# main.net
KiCad netlist of a schematic drawn in EAGLE
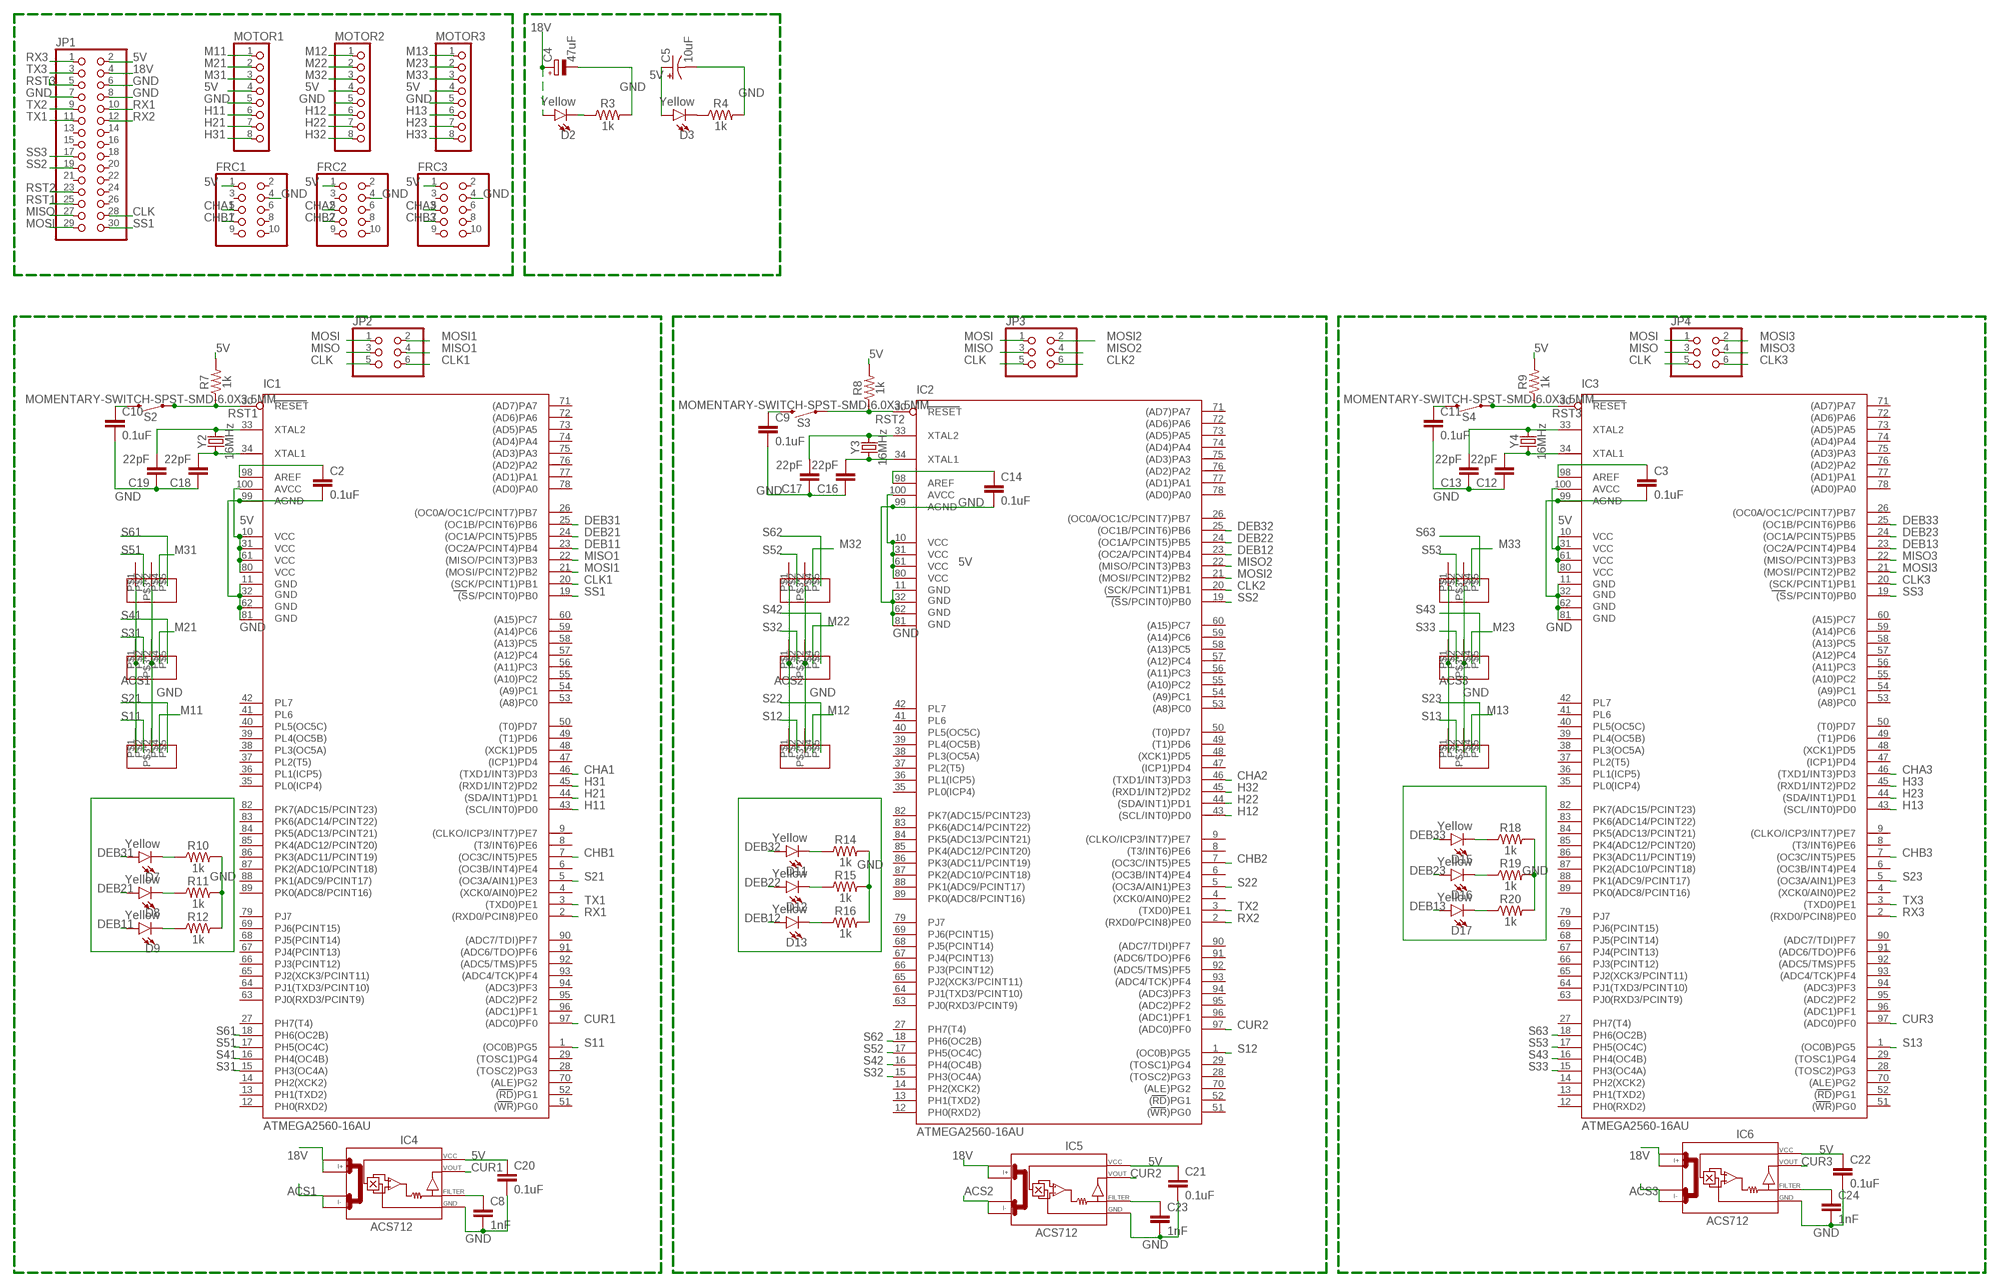
[diagram p0: schematic, sheet 1]

(export (version "E")
  (design (tool "Eeschema 10.0.6"))
  (components
    (comp (ref "C2")
      (value "0.1uF")
      (footprint "eagle-import:0603")
      (libsource (lib "eagle-import") (part "0.1UF-0603-25V-5%"))
    )
    (comp (ref "C3")
      (value "0.1uF")
      (footprint "eagle-import:0603")
      (libsource (lib "eagle-import") (part "0.1UF-0603-25V-5%"))
    )
    (comp (ref "C4")
      (value "47uF")
      (footprint "eagle-import:TAP5-60")
      (libsource (lib "eagle-import") (part "CPOL-EUTAP5-60"))
    )
    (comp (ref "C5")
      (value "10uF")
      (footprint "eagle-import:0603-POLAR")
      (libsource (lib "eagle-import") (part "10UF-POLAR-0603-6.3V-20%(TANT)"))
    )
    (comp (ref "C8")
      (value "1nF")
      (footprint "eagle-import:0603")
      (libsource (lib "eagle-import") (part "1.0NF/1000PF-0603-50V-10%"))
    )
    (comp (ref "C9")
      (value "0.1uF")
      (footprint "eagle-import:0603")
      (libsource (lib "eagle-import") (part "0.1UF-0603-25V-5%"))
    )
    (comp (ref "C10")
      (value "0.1uF")
      (footprint "eagle-import:0603")
      (libsource (lib "eagle-import") (part "0.1UF-0603-25V-5%"))
    )
    (comp (ref "C11")
      (value "0.1uF")
      (footprint "eagle-import:0603")
      (libsource (lib "eagle-import") (part "0.1UF-0603-25V-5%"))
    )
    (comp (ref "C12")
      (value "22pF")
      (footprint "eagle-import:0603")
      (libsource (lib "eagle-import") (part "22PF-0603-50V-5%"))
    )
    (comp (ref "C13")
      (value "22pF")
      (footprint "eagle-import:0603")
      (libsource (lib "eagle-import") (part "22PF-0603-50V-5%"))
    )
    (comp (ref "C14")
      (value "0.1uF")
      (footprint "eagle-import:0603")
      (libsource (lib "eagle-import") (part "0.1UF-0603-25V-5%"))
    )
    (comp (ref "C16")
      (value "22pF")
      (footprint "eagle-import:0603")
      (libsource (lib "eagle-import") (part "22PF-0603-50V-5%"))
    )
    (comp (ref "C17")
      (value "22pF")
      (footprint "eagle-import:0603")
      (libsource (lib "eagle-import") (part "22PF-0603-50V-5%"))
    )
    (comp (ref "C18")
      (value "22pF")
      (footprint "eagle-import:0603")
      (libsource (lib "eagle-import") (part "22PF-0603-50V-5%"))
    )
    (comp (ref "C19")
      (value "22pF")
      (footprint "eagle-import:0603")
      (libsource (lib "eagle-import") (part "22PF-0603-50V-5%"))
    )
    (comp (ref "C20")
      (value "0.1uF")
      (footprint "eagle-import:0603")
      (libsource (lib "eagle-import") (part "0.1UF-0603-25V-5%"))
    )
    (comp (ref "C21")
      (value "0.1uF")
      (footprint "eagle-import:0603")
      (libsource (lib "eagle-import") (part "0.1UF-0603-25V-5%"))
    )
    (comp (ref "C22")
      (value "0.1uF")
      (footprint "eagle-import:0603")
      (libsource (lib "eagle-import") (part "0.1UF-0603-25V-5%"))
    )
    (comp (ref "C23")
      (value "1nF")
      (footprint "eagle-import:0603")
      (libsource (lib "eagle-import") (part "1.0NF/1000PF-0603-50V-10%"))
    )
    (comp (ref "C24")
      (value "1nF")
      (footprint "eagle-import:0603")
      (libsource (lib "eagle-import") (part "1.0NF/1000PF-0603-50V-10%"))
    )
    (comp (ref "D2")
      (value "Yellow")
      (footprint "eagle-import:LED-0603")
      (libsource (lib "eagle-import") (part "LED-YELLOW0603"))
    )
    (comp (ref "D3")
      (value "Yellow")
      (footprint "eagle-import:LED-0603")
      (libsource (lib "eagle-import") (part "LED-YELLOW0603"))
    )
    (comp (ref "D7")
      (value "Yellow")
      (footprint "eagle-import:LED-0603")
      (libsource (lib "eagle-import") (part "LED-YELLOW0603"))
    )
    (comp (ref "D8")
      (value "Yellow")
      (footprint "eagle-import:LED-0603")
      (libsource (lib "eagle-import") (part "LED-YELLOW0603"))
    )
    (comp (ref "D9")
      (value "Yellow")
      (footprint "eagle-import:LED-0603")
      (libsource (lib "eagle-import") (part "LED-YELLOW0603"))
    )
    (comp (ref "D11")
      (value "Yellow")
      (footprint "eagle-import:LED-0603")
      (libsource (lib "eagle-import") (part "LED-YELLOW0603"))
    )
    (comp (ref "D12")
      (value "Yellow")
      (footprint "eagle-import:LED-0603")
      (libsource (lib "eagle-import") (part "LED-YELLOW0603"))
    )
    (comp (ref "D13")
      (value "Yellow")
      (footprint "eagle-import:LED-0603")
      (libsource (lib "eagle-import") (part "LED-YELLOW0603"))
    )
    (comp (ref "D15")
      (value "Yellow")
      (footprint "eagle-import:LED-0603")
      (libsource (lib "eagle-import") (part "LED-YELLOW0603"))
    )
    (comp (ref "D16")
      (value "Yellow")
      (footprint "eagle-import:LED-0603")
      (libsource (lib "eagle-import") (part "LED-YELLOW0603"))
    )
    (comp (ref "D17")
      (value "Yellow")
      (footprint "eagle-import:LED-0603")
      (libsource (lib "eagle-import") (part "LED-YELLOW0603"))
    )
    (comp (ref "FRC1")
      (value "PINHD-2X5")
      (footprint "eagle-import:2X05")
      (libsource (lib "eagle-import") (part "PINHD-2X5"))
    )
    (comp (ref "FRC2")
      (value "PINHD-2X5")
      (footprint "eagle-import:2X05")
      (libsource (lib "eagle-import") (part "PINHD-2X5"))
    )
    (comp (ref "FRC3")
      (value "PINHD-2X5")
      (footprint "eagle-import:2X05")
      (libsource (lib "eagle-import") (part "PINHD-2X5"))
    )
    (comp (ref "IC1")
      (value "ATMEGA2560-16AU")
      (footprint "eagle-import:TQFP100")
      (libsource (lib "eagle-import") (part "ATMEGAAU2560-16"))
    )
    (comp (ref "IC2")
      (value "ATMEGA2560-16AU")
      (footprint "eagle-import:TQFP100")
      (libsource (lib "eagle-import") (part "ATMEGAAU2560-16"))
    )
    (comp (ref "IC3")
      (value "ATMEGA2560-16AU")
      (footprint "eagle-import:TQFP100")
      (libsource (lib "eagle-import") (part "ATMEGAAU2560-16"))
    )
    (comp (ref "IC4")
      (value "ACS712")
      (footprint "eagle-import:SO08")
      (libsource (lib "eagle-import") (part "ACS712"))
    )
    (comp (ref "IC5")
      (value "ACS712")
      (footprint "eagle-import:SO08")
      (libsource (lib "eagle-import") (part "ACS712"))
    )
    (comp (ref "IC6")
      (value "ACS712")
      (footprint "eagle-import:SO08")
      (libsource (lib "eagle-import") (part "ACS712"))
    )
    (comp (ref "JP1")
      (value "PINHD-2X15/90")
      (footprint "eagle-import:2X15_90")
      (libsource (lib "eagle-import") (part "PINHD-2X15/90"))
    )
    (comp (ref "JP2")
      (value "PINHD-2X3")
      (footprint "eagle-import:2X03")
      (libsource (lib "eagle-import") (part "PINHD-2X3"))
    )
    (comp (ref "JP3")
      (value "PINHD-2X3")
      (footprint "eagle-import:2X03")
      (libsource (lib "eagle-import") (part "PINHD-2X3"))
    )
    (comp (ref "JP4")
      (value "PINHD-2X3")
      (footprint "eagle-import:2X03")
      (libsource (lib "eagle-import") (part "PINHD-2X3"))
    )
    (comp (ref "MIC1")
      (value "UC2950")
      (footprint "eagle-import:UC2950")
      (libsource (lib "eagle-import") (part "UC2950"))
    )
    (comp (ref "MIC2")
      (value "UC2950")
      (footprint "eagle-import:UC2950")
      (libsource (lib "eagle-import") (part "UC2950"))
    )
    (comp (ref "MIC3")
      (value "UC2950")
      (footprint "eagle-import:UC2950")
      (libsource (lib "eagle-import") (part "UC2950"))
    )
    (comp (ref "MIC4")
      (value "UC2950")
      (footprint "eagle-import:UC2950")
      (libsource (lib "eagle-import") (part "UC2950"))
    )
    (comp (ref "MIC5")
      (value "UC2950")
      (footprint "eagle-import:UC2950")
      (libsource (lib "eagle-import") (part "UC2950"))
    )
    (comp (ref "MIC6")
      (value "UC2950")
      (footprint "eagle-import:UC2950")
      (libsource (lib "eagle-import") (part "UC2950"))
    )
    (comp (ref "MIC7")
      (value "UC2950")
      (footprint "eagle-import:UC2950")
      (libsource (lib "eagle-import") (part "UC2950"))
    )
    (comp (ref "MIC8")
      (value "UC2950")
      (footprint "eagle-import:UC2950")
      (libsource (lib "eagle-import") (part "UC2950"))
    )
    (comp (ref "MIC9")
      (value "UC2950")
      (footprint "eagle-import:UC2950")
      (libsource (lib "eagle-import") (part "UC2950"))
    )
    (comp (ref "MOTOR1")
      (value "PINHD-1X8")
      (footprint "eagle-import:1X08")
      (libsource (lib "eagle-import") (part "PINHD-1X8"))
    )
    (comp (ref "MOTOR2")
      (value "PINHD-1X8")
      (footprint "eagle-import:1X08")
      (libsource (lib "eagle-import") (part "PINHD-1X8"))
    )
    (comp (ref "MOTOR3")
      (value "PINHD-1X8")
      (footprint "eagle-import:1X08")
      (libsource (lib "eagle-import") (part "PINHD-1X8"))
    )
    (comp (ref "R3")
      (value "1k")
      (footprint "eagle-import:0603")
      (libsource (lib "eagle-import") (part "1KOHM-0603-1/10W-1%"))
    )
    (comp (ref "R4")
      (value "1k")
      (footprint "eagle-import:0603")
      (libsource (lib "eagle-import") (part "1KOHM-0603-1/10W-1%"))
    )
    (comp (ref "R7")
      (value "1k")
      (footprint "eagle-import:0603")
      (libsource (lib "eagle-import") (part "1KOHM-0603-1/10W-1%"))
    )
    (comp (ref "R8")
      (value "1k")
      (footprint "eagle-import:0603")
      (libsource (lib "eagle-import") (part "1KOHM-0603-1/10W-1%"))
    )
    (comp (ref "R9")
      (value "1k")
      (footprint "eagle-import:0603")
      (libsource (lib "eagle-import") (part "1KOHM-0603-1/10W-1%"))
    )
    (comp (ref "R10")
      (value "1k")
      (footprint "eagle-import:0603")
      (libsource (lib "eagle-import") (part "1KOHM-0603-1/10W-1%"))
    )
    (comp (ref "R11")
      (value "1k")
      (footprint "eagle-import:0603")
      (libsource (lib "eagle-import") (part "1KOHM-0603-1/10W-1%"))
    )
    (comp (ref "R12")
      (value "1k")
      (footprint "eagle-import:0603")
      (libsource (lib "eagle-import") (part "1KOHM-0603-1/10W-1%"))
    )
    (comp (ref "R14")
      (value "1k")
      (footprint "eagle-import:0603")
      (libsource (lib "eagle-import") (part "1KOHM-0603-1/10W-1%"))
    )
    (comp (ref "R15")
      (value "1k")
      (footprint "eagle-import:0603")
      (libsource (lib "eagle-import") (part "1KOHM-0603-1/10W-1%"))
    )
    (comp (ref "R16")
      (value "1k")
      (footprint "eagle-import:0603")
      (libsource (lib "eagle-import") (part "1KOHM-0603-1/10W-1%"))
    )
    (comp (ref "R18")
      (value "1k")
      (footprint "eagle-import:0603")
      (libsource (lib "eagle-import") (part "1KOHM-0603-1/10W-1%"))
    )
    (comp (ref "R19")
      (value "1k")
      (footprint "eagle-import:0603")
      (libsource (lib "eagle-import") (part "1KOHM-0603-1/10W-1%"))
    )
    (comp (ref "R20")
      (value "1k")
      (footprint "eagle-import:0603")
      (libsource (lib "eagle-import") (part "1KOHM-0603-1/10W-1%"))
    )
    (comp (ref "S2")
      (value "MOMENTARY-SWITCH-SPST-SMD-6.0X3.5MM")
      (footprint "eagle-import:TACTILE_SWITCH_SMD_6.0X3.5MM")
      (libsource (lib "eagle-import") (part "MOMENTARY-SWITCH-SPST-SMD-6.0X3.5MM"))
    )
    (comp (ref "S3")
      (value "MOMENTARY-SWITCH-SPST-SMD-6.0X3.5MM")
      (footprint "eagle-import:TACTILE_SWITCH_SMD_6.0X3.5MM")
      (libsource (lib "eagle-import") (part "MOMENTARY-SWITCH-SPST-SMD-6.0X3.5MM"))
    )
    (comp (ref "S4")
      (value "MOMENTARY-SWITCH-SPST-SMD-6.0X3.5MM")
      (footprint "eagle-import:TACTILE_SWITCH_SMD_6.0X3.5MM")
      (libsource (lib "eagle-import") (part "MOMENTARY-SWITCH-SPST-SMD-6.0X3.5MM"))
    )
    (comp (ref "Y2")
      (value "16MHz")
      (footprint "eagle-import:CRYSTAL-SMD-5X3.2-4PAD")
      (libsource (lib "eagle-import") (part "CRYSTAL-16MHZSMD-5X3.2"))
    )
    (comp (ref "Y3")
      (value "16MHz")
      (footprint "eagle-import:CRYSTAL-SMD-5X3.2-4PAD")
      (libsource (lib "eagle-import") (part "CRYSTAL-16MHZSMD-5X3.2"))
    )
    (comp (ref "Y4")
      (value "16MHz")
      (footprint "eagle-import:CRYSTAL-SMD-5X3.2-4PAD")
      (libsource (lib "eagle-import") (part "CRYSTAL-16MHZSMD-5X3.2"))
    )
  )
  (nets
    (net (code "1") (name "/5V") (class "Default")
      (node (ref "C20") (pin "1") (pinfunction "1_1") (pintype "passive"))
      (node (ref "C21") (pin "1") (pinfunction "1_1") (pintype "passive"))
      (node (ref "C22") (pin "1") (pinfunction "1_1") (pintype "passive"))
      (node (ref "C5") (pin "+") (pinfunction "+_+") (pintype "passive"))
      (node (ref "D3") (pin "A") (pinfunction "A_A") (pintype "passive"))
      (node (ref "FRC1") (pin "1") (pinfunction "1_1") (pintype "passive"))
      (node (ref "FRC2") (pin "1") (pinfunction "1_1") (pintype "passive"))
      (node (ref "FRC3") (pin "1") (pinfunction "1_1") (pintype "passive"))
      (node (ref "IC1") (pin "10") (pinfunction "VCC_10") (pintype "power_in"))
      (node (ref "IC1") (pin "100") (pinfunction "AVCC_100") (pintype "power_in"))
      (node (ref "IC1") (pin "31") (pinfunction "VCC1_31") (pintype "power_in"))
      (node (ref "IC1") (pin "61") (pinfunction "VCC2_61") (pintype "power_in"))
      (node (ref "IC1") (pin "80") (pinfunction "VCC3_80") (pintype "power_in"))
      (node (ref "IC2") (pin "10") (pinfunction "VCC_10") (pintype "power_in"))
      (node (ref "IC2") (pin "100") (pinfunction "AVCC_100") (pintype "power_in"))
      (node (ref "IC2") (pin "31") (pinfunction "VCC1_31") (pintype "power_in"))
      (node (ref "IC2") (pin "61") (pinfunction "VCC2_61") (pintype "power_in"))
      (node (ref "IC2") (pin "80") (pinfunction "VCC3_80") (pintype "power_in"))
      (node (ref "IC3") (pin "10") (pinfunction "VCC_10") (pintype "power_in"))
      (node (ref "IC3") (pin "100") (pinfunction "AVCC_100") (pintype "power_in"))
      (node (ref "IC3") (pin "31") (pinfunction "VCC1_31") (pintype "power_in"))
      (node (ref "IC3") (pin "61") (pinfunction "VCC2_61") (pintype "power_in"))
      (node (ref "IC3") (pin "80") (pinfunction "VCC3_80") (pintype "power_in"))
      (node (ref "IC4") (pin "8") (pinfunction "VCC_8") (pintype "power_in"))
      (node (ref "IC5") (pin "8") (pinfunction "VCC_8") (pintype "power_in"))
      (node (ref "IC6") (pin "8") (pinfunction "VCC_8") (pintype "power_in"))
      (node (ref "JP1") (pin "2") (pinfunction "2_2") (pintype "passive"))
      (node (ref "MOTOR1") (pin "4") (pinfunction "4_4") (pintype "passive"))
      (node (ref "MOTOR2") (pin "4") (pinfunction "4_4") (pintype "passive"))
      (node (ref "MOTOR3") (pin "4") (pinfunction "4_4") (pintype "passive"))
      (node (ref "R7") (pin "2") (pinfunction "2_2") (pintype "passive"))
      (node (ref "R8") (pin "2") (pinfunction "2_2") (pintype "passive"))
      (node (ref "R9") (pin "2") (pinfunction "2_2") (pintype "passive"))
    )
    (net (code "2") (name "/18V") (class "Default")
      (node (ref "C4") (pin "+") (pinfunction "+_+") (pintype "passive"))
      (node (ref "D2") (pin "A") (pinfunction "A_A") (pintype "passive"))
      (node (ref "IC4") (pin "1") (pinfunction "I+_0_1") (pintype "bidirectional"))
      (node (ref "IC5") (pin "1") (pinfunction "I+_0_1") (pintype "bidirectional"))
      (node (ref "IC6") (pin "1") (pinfunction "I+_0_1") (pintype "bidirectional"))
      (node (ref "JP1") (pin "4") (pinfunction "4_4") (pintype "passive"))
    )
    (net (code "3") (name "/ACS1") (class "Default")
      (node (ref "IC4") (pin "3") (pinfunction "I-_0_3") (pintype "bidirectional"))
      (node (ref "MIC1") (pin "P$1") (pinfunction "P$1_P$1") (pintype "bidirectional"))
      (node (ref "MIC2") (pin "P$1") (pinfunction "P$1_P$1") (pintype "bidirectional"))
      (node (ref "MIC3") (pin "P$1") (pinfunction "P$1_P$1") (pintype "bidirectional"))
    )
    (net (code "4") (name "/ACS2") (class "Default")
      (node (ref "IC5") (pin "3") (pinfunction "I-_0_3") (pintype "bidirectional"))
      (node (ref "MIC4") (pin "P$1") (pinfunction "P$1_P$1") (pintype "bidirectional"))
      (node (ref "MIC5") (pin "P$1") (pinfunction "P$1_P$1") (pintype "bidirectional"))
      (node (ref "MIC6") (pin "P$1") (pinfunction "P$1_P$1") (pintype "bidirectional"))
    )
    (net (code "5") (name "/ACS3") (class "Default")
      (node (ref "IC6") (pin "3") (pinfunction "I-_0_3") (pintype "bidirectional"))
      (node (ref "MIC7") (pin "P$1") (pinfunction "P$1_P$1") (pintype "bidirectional"))
      (node (ref "MIC8") (pin "P$1") (pinfunction "P$1_P$1") (pintype "bidirectional"))
      (node (ref "MIC9") (pin "P$1") (pinfunction "P$1_P$1") (pintype "bidirectional"))
    )
    (net (code "6") (name "/CHA1") (class "Default")
      (node (ref "FRC1") (pin "5") (pinfunction "5_5") (pintype "passive"))
      (node (ref "IC1") (pin "46") (pinfunction "(TXD1/INT3)PD3_46") (pintype "bidirectional"))
    )
    (net (code "7") (name "/CHA2") (class "Default")
      (node (ref "FRC2") (pin "5") (pinfunction "5_5") (pintype "passive"))
      (node (ref "IC2") (pin "46") (pinfunction "(TXD1/INT3)PD3_46") (pintype "bidirectional"))
    )
    (net (code "8") (name "/CHA3") (class "Default")
      (node (ref "FRC3") (pin "5") (pinfunction "5_5") (pintype "passive"))
      (node (ref "IC3") (pin "46") (pinfunction "(TXD1/INT3)PD3_46") (pintype "bidirectional"))
    )
    (net (code "9") (name "/CHB1") (class "Default")
      (node (ref "FRC1") (pin "7") (pinfunction "7_7") (pintype "passive"))
      (node (ref "IC1") (pin "7") (pinfunction "(OC3C/INT5)PE5_7") (pintype "bidirectional"))
    )
    (net (code "10") (name "/CHB2") (class "Default")
      (node (ref "FRC2") (pin "7") (pinfunction "7_7") (pintype "passive"))
      (node (ref "IC2") (pin "7") (pinfunction "(OC3C/INT5)PE5_7") (pintype "bidirectional"))
    )
    (net (code "11") (name "/CHB3") (class "Default")
      (node (ref "FRC3") (pin "7") (pinfunction "7_7") (pintype "passive"))
      (node (ref "IC3") (pin "7") (pinfunction "(OC3C/INT5)PE5_7") (pintype "bidirectional"))
    )
    (net (code "12") (name "/CLK") (class "Default")
      (node (ref "JP1") (pin "28") (pinfunction "28_28") (pintype "passive"))
      (node (ref "JP2") (pin "5") (pinfunction "5_5") (pintype "passive"))
      (node (ref "JP3") (pin "5") (pinfunction "5_5") (pintype "passive"))
      (node (ref "JP4") (pin "5") (pinfunction "5_5") (pintype "passive"))
    )
    (net (code "13") (name "/CLK1") (class "Default")
      (node (ref "IC1") (pin "20") (pinfunction "(SCK/PCINT1)PB1_20") (pintype "bidirectional"))
      (node (ref "JP2") (pin "6") (pinfunction "6_6") (pintype "passive"))
    )
    (net (code "14") (name "/CLK2") (class "Default")
      (node (ref "IC2") (pin "20") (pinfunction "(SCK/PCINT1)PB1_20") (pintype "bidirectional"))
      (node (ref "JP3") (pin "6") (pinfunction "6_6") (pintype "passive"))
    )
    (net (code "15") (name "/CLK3") (class "Default")
      (node (ref "IC3") (pin "20") (pinfunction "(SCK/PCINT1)PB1_20") (pintype "bidirectional"))
      (node (ref "JP4") (pin "6") (pinfunction "6_6") (pintype "passive"))
    )
    (net (code "16") (name "/CUR1") (class "Default")
      (node (ref "IC1") (pin "97") (pinfunction "(ADC0)PF0_97") (pintype "bidirectional"))
      (node (ref "IC4") (pin "7") (pinfunction "VOUT_7") (pintype "output"))
    )
    (net (code "17") (name "/CUR2") (class "Default")
      (node (ref "IC2") (pin "97") (pinfunction "(ADC0)PF0_97") (pintype "bidirectional"))
      (node (ref "IC5") (pin "7") (pinfunction "VOUT_7") (pintype "output"))
    )
    (net (code "18") (name "/CUR3") (class "Default")
      (node (ref "IC3") (pin "97") (pinfunction "(ADC0)PF0_97") (pintype "bidirectional"))
      (node (ref "IC6") (pin "7") (pinfunction "VOUT_7") (pintype "output"))
    )
    (net (code "19") (name "/DEB11") (class "Default")
      (node (ref "D9") (pin "A") (pinfunction "A_A") (pintype "passive"))
      (node (ref "IC1") (pin "23") (pinfunction "(OC2A/PCINT4)PB4_23") (pintype "bidirectional"))
    )
    (net (code "20") (name "/DEB12") (class "Default")
      (node (ref "D13") (pin "A") (pinfunction "A_A") (pintype "passive"))
      (node (ref "IC2") (pin "23") (pinfunction "(OC2A/PCINT4)PB4_23") (pintype "bidirectional"))
    )
    (net (code "21") (name "/DEB13") (class "Default")
      (node (ref "D17") (pin "A") (pinfunction "A_A") (pintype "passive"))
      (node (ref "IC3") (pin "23") (pinfunction "(OC2A/PCINT4)PB4_23") (pintype "bidirectional"))
    )
    (net (code "22") (name "/DEB21") (class "Default")
      (node (ref "D8") (pin "A") (pinfunction "A_A") (pintype "passive"))
      (node (ref "IC1") (pin "24") (pinfunction "(OC1A/PCINT5)PB5_24") (pintype "bidirectional"))
    )
    (net (code "23") (name "/DEB22") (class "Default")
      (node (ref "D12") (pin "A") (pinfunction "A_A") (pintype "passive"))
      (node (ref "IC2") (pin "24") (pinfunction "(OC1A/PCINT5)PB5_24") (pintype "bidirectional"))
    )
    (net (code "24") (name "/DEB23") (class "Default")
      (node (ref "D16") (pin "A") (pinfunction "A_A") (pintype "passive"))
      (node (ref "IC3") (pin "24") (pinfunction "(OC1A/PCINT5)PB5_24") (pintype "bidirectional"))
    )
    (net (code "25") (name "/DEB31") (class "Default")
      (node (ref "D7") (pin "A") (pinfunction "A_A") (pintype "passive"))
      (node (ref "IC1") (pin "25") (pinfunction "(OC1B/PCINT6)PB6_25") (pintype "bidirectional"))
    )
    (net (code "26") (name "/DEB32") (class "Default")
      (node (ref "D11") (pin "A") (pinfunction "A_A") (pintype "passive"))
      (node (ref "IC2") (pin "25") (pinfunction "(OC1B/PCINT6)PB6_25") (pintype "bidirectional"))
    )
    (net (code "27") (name "/DEB33") (class "Default")
      (node (ref "D15") (pin "A") (pinfunction "A_A") (pintype "passive"))
      (node (ref "IC3") (pin "25") (pinfunction "(OC1B/PCINT6)PB6_25") (pintype "bidirectional"))
    )
    (net (code "28") (name "/GND") (class "Default")
      (node (ref "C10") (pin "2") (pinfunction "2_2") (pintype "passive"))
      (node (ref "C11") (pin "2") (pinfunction "2_2") (pintype "passive"))
      (node (ref "C12") (pin "1") (pinfunction "1_1") (pintype "passive"))
      (node (ref "C13") (pin "1") (pinfunction "1_1") (pintype "passive"))
      (node (ref "C14") (pin "2") (pinfunction "2_2") (pintype "passive"))
      (node (ref "C16") (pin "1") (pinfunction "1_1") (pintype "passive"))
      (node (ref "C17") (pin "1") (pinfunction "1_1") (pintype "passive"))
      (node (ref "C18") (pin "1") (pinfunction "1_1") (pintype "passive"))
      (node (ref "C19") (pin "1") (pinfunction "1_1") (pintype "passive"))
      (node (ref "C2") (pin "2") (pinfunction "2_2") (pintype "passive"))
      (node (ref "C20") (pin "2") (pinfunction "2_2") (pintype "passive"))
      (node (ref "C21") (pin "2") (pinfunction "2_2") (pintype "passive"))
      (node (ref "C22") (pin "2") (pinfunction "2_2") (pintype "passive"))
      (node (ref "C23") (pin "2") (pinfunction "2_2") (pintype "passive"))
      (node (ref "C24") (pin "2") (pinfunction "2_2") (pintype "passive"))
      (node (ref "C3") (pin "2") (pinfunction "2_2") (pintype "passive"))
      (node (ref "C4") (pin "-") (pinfunction "-_-") (pintype "passive"))
      (node (ref "C5") (pin "-") (pinfunction "-_-") (pintype "passive"))
      (node (ref "C8") (pin "2") (pinfunction "2_2") (pintype "passive"))
      (node (ref "C9") (pin "2") (pinfunction "2_2") (pintype "passive"))
      (node (ref "FRC1") (pin "4") (pinfunction "4_4") (pintype "passive"))
      (node (ref "FRC2") (pin "4") (pinfunction "4_4") (pintype "passive"))
      (node (ref "FRC3") (pin "4") (pinfunction "4_4") (pintype "passive"))
      (node (ref "IC1") (pin "11") (pinfunction "GND_11") (pintype "power_in"))
      (node (ref "IC1") (pin "32") (pinfunction "GND1_32") (pintype "power_in"))
      (node (ref "IC1") (pin "62") (pinfunction "GND2_62") (pintype "power_in"))
      (node (ref "IC1") (pin "81") (pinfunction "GND3_81") (pintype "power_in"))
      (node (ref "IC1") (pin "99") (pinfunction "AGND_99") (pintype "power_in"))
      (node (ref "IC2") (pin "11") (pinfunction "GND_11") (pintype "power_in"))
      (node (ref "IC2") (pin "32") (pinfunction "GND1_32") (pintype "power_in"))
      (node (ref "IC2") (pin "62") (pinfunction "GND2_62") (pintype "power_in"))
      (node (ref "IC2") (pin "81") (pinfunction "GND3_81") (pintype "power_in"))
      (node (ref "IC2") (pin "99") (pinfunction "AGND_99") (pintype "power_in"))
      (node (ref "IC3") (pin "11") (pinfunction "GND_11") (pintype "power_in"))
      (node (ref "IC3") (pin "32") (pinfunction "GND1_32") (pintype "power_in"))
      (node (ref "IC3") (pin "62") (pinfunction "GND2_62") (pintype "power_in"))
      (node (ref "IC3") (pin "81") (pinfunction "GND3_81") (pintype "power_in"))
      (node (ref "IC3") (pin "99") (pinfunction "AGND_99") (pintype "power_in"))
      (node (ref "IC4") (pin "5") (pinfunction "GND_5") (pintype "power_in"))
      (node (ref "IC5") (pin "5") (pinfunction "GND_5") (pintype "power_in"))
      (node (ref "IC6") (pin "5") (pinfunction "GND_5") (pintype "power_in"))
      (node (ref "JP1") (pin "6") (pinfunction "6_6") (pintype "passive"))
      (node (ref "JP1") (pin "7") (pinfunction "7_7") (pintype "passive"))
      (node (ref "JP1") (pin "8") (pinfunction "8_8") (pintype "passive"))
      (node (ref "MIC1") (pin "P$3") (pinfunction "P$3_P$3") (pintype "bidirectional"))
      (node (ref "MIC1") (pin "P$6") (pinfunction "P$3_P$6") (pintype "bidirectional"))
      (node (ref "MIC2") (pin "P$3") (pinfunction "P$3_P$3") (pintype "bidirectional"))
      (node (ref "MIC2") (pin "P$6") (pinfunction "P$3_P$6") (pintype "bidirectional"))
      (node (ref "MIC3") (pin "P$3") (pinfunction "P$3_P$3") (pintype "bidirectional"))
      (node (ref "MIC3") (pin "P$6") (pinfunction "P$3_P$6") (pintype "bidirectional"))
      (node (ref "MIC4") (pin "P$3") (pinfunction "P$3_P$3") (pintype "bidirectional"))
      (node (ref "MIC4") (pin "P$6") (pinfunction "P$3_P$6") (pintype "bidirectional"))
      (node (ref "MIC5") (pin "P$3") (pinfunction "P$3_P$3") (pintype "bidirectional"))
      (node (ref "MIC5") (pin "P$6") (pinfunction "P$3_P$6") (pintype "bidirectional"))
      (node (ref "MIC6") (pin "P$3") (pinfunction "P$3_P$3") (pintype "bidirectional"))
      (node (ref "MIC6") (pin "P$6") (pinfunction "P$3_P$6") (pintype "bidirectional"))
      (node (ref "MIC7") (pin "P$3") (pinfunction "P$3_P$3") (pintype "bidirectional"))
      (node (ref "MIC7") (pin "P$6") (pinfunction "P$3_P$6") (pintype "bidirectional"))
      (node (ref "MIC8") (pin "P$3") (pinfunction "P$3_P$3") (pintype "bidirectional"))
      (node (ref "MIC8") (pin "P$6") (pinfunction "P$3_P$6") (pintype "bidirectional"))
      (node (ref "MIC9") (pin "P$3") (pinfunction "P$3_P$3") (pintype "bidirectional"))
      (node (ref "MIC9") (pin "P$6") (pinfunction "P$3_P$6") (pintype "bidirectional"))
      (node (ref "MOTOR1") (pin "5") (pinfunction "5_5") (pintype "passive"))
      (node (ref "MOTOR2") (pin "5") (pinfunction "5_5") (pintype "passive"))
      (node (ref "MOTOR3") (pin "5") (pinfunction "5_5") (pintype "passive"))
      (node (ref "R10") (pin "2") (pinfunction "2_2") (pintype "passive"))
      (node (ref "R11") (pin "2") (pinfunction "2_2") (pintype "passive"))
      (node (ref "R12") (pin "2") (pinfunction "2_2") (pintype "passive"))
      (node (ref "R14") (pin "2") (pinfunction "2_2") (pintype "passive"))
      (node (ref "R15") (pin "2") (pinfunction "2_2") (pintype "passive"))
      (node (ref "R16") (pin "2") (pinfunction "2_2") (pintype "passive"))
      (node (ref "R18") (pin "2") (pinfunction "2_2") (pintype "passive"))
      (node (ref "R19") (pin "2") (pinfunction "2_2") (pintype "passive"))
      (node (ref "R20") (pin "2") (pinfunction "2_2") (pintype "passive"))
      (node (ref "R3") (pin "2") (pinfunction "2_2") (pintype "passive"))
      (node (ref "R4") (pin "2") (pinfunction "2_2") (pintype "passive"))
    )
    (net (code "29") (name "/H11") (class "Default")
      (node (ref "IC1") (pin "43") (pinfunction "(SCL/INT0)PD0_43") (pintype "bidirectional"))
      (node (ref "MOTOR1") (pin "6") (pinfunction "6_6") (pintype "passive"))
    )
    (net (code "30") (name "/H12") (class "Default")
      (node (ref "IC2") (pin "43") (pinfunction "(SCL/INT0)PD0_43") (pintype "bidirectional"))
      (node (ref "MOTOR2") (pin "6") (pinfunction "6_6") (pintype "passive"))
    )
    (net (code "31") (name "/H13") (class "Default")
      (node (ref "IC3") (pin "43") (pinfunction "(SCL/INT0)PD0_43") (pintype "bidirectional"))
      (node (ref "MOTOR3") (pin "6") (pinfunction "6_6") (pintype "passive"))
    )
    (net (code "32") (name "/H21") (class "Default")
      (node (ref "IC1") (pin "44") (pinfunction "(SDA/INT1)PD1_44") (pintype "bidirectional"))
      (node (ref "MOTOR1") (pin "7") (pinfunction "7_7") (pintype "passive"))
    )
    (net (code "33") (name "/H22") (class "Default")
      (node (ref "IC2") (pin "44") (pinfunction "(SDA/INT1)PD1_44") (pintype "bidirectional"))
      (node (ref "MOTOR2") (pin "7") (pinfunction "7_7") (pintype "passive"))
    )
    (net (code "34") (name "/H23") (class "Default")
      (node (ref "IC3") (pin "44") (pinfunction "(SDA/INT1)PD1_44") (pintype "bidirectional"))
      (node (ref "MOTOR3") (pin "7") (pinfunction "7_7") (pintype "passive"))
    )
    (net (code "35") (name "/H31") (class "Default")
      (node (ref "IC1") (pin "45") (pinfunction "(RXD1/INT2)PD2_45") (pintype "bidirectional"))
      (node (ref "MOTOR1") (pin "8") (pinfunction "8_8") (pintype "passive"))
    )
    (net (code "36") (name "/H32") (class "Default")
      (node (ref "IC2") (pin "45") (pinfunction "(RXD1/INT2)PD2_45") (pintype "bidirectional"))
      (node (ref "MOTOR2") (pin "8") (pinfunction "8_8") (pintype "passive"))
    )
    (net (code "37") (name "/H33") (class "Default")
      (node (ref "IC3") (pin "45") (pinfunction "(RXD1/INT2)PD2_45") (pintype "bidirectional"))
      (node (ref "MOTOR3") (pin "8") (pinfunction "8_8") (pintype "passive"))
    )
    (net (code "38") (name "/M11") (class "Default")
      (node (ref "MIC3") (pin "P$4") (pinfunction "P$4_P$4") (pintype "bidirectional"))
      (node (ref "MOTOR1") (pin "1") (pinfunction "1_1") (pintype "passive"))
    )
    (net (code "39") (name "/M12") (class "Default")
      (node (ref "MIC6") (pin "P$4") (pinfunction "P$4_P$4") (pintype "bidirectional"))
      (node (ref "MOTOR2") (pin "1") (pinfunction "1_1") (pintype "passive"))
    )
    (net (code "40") (name "/M13") (class "Default")
      (node (ref "MIC7") (pin "P$4") (pinfunction "P$4_P$4") (pintype "bidirectional"))
      (node (ref "MOTOR3") (pin "1") (pinfunction "1_1") (pintype "passive"))
    )
    (net (code "41") (name "/M21") (class "Default")
      (node (ref "MIC2") (pin "P$4") (pinfunction "P$4_P$4") (pintype "bidirectional"))
      (node (ref "MOTOR1") (pin "2") (pinfunction "2_2") (pintype "passive"))
    )
    (net (code "42") (name "/M22") (class "Default")
      (node (ref "MIC5") (pin "P$4") (pinfunction "P$4_P$4") (pintype "bidirectional"))
      (node (ref "MOTOR2") (pin "2") (pinfunction "2_2") (pintype "passive"))
    )
    (net (code "43") (name "/M23") (class "Default")
      (node (ref "MIC8") (pin "P$4") (pinfunction "P$4_P$4") (pintype "bidirectional"))
      (node (ref "MOTOR3") (pin "2") (pinfunction "2_2") (pintype "passive"))
    )
    (net (code "44") (name "/M31") (class "Default")
      (node (ref "MIC1") (pin "P$4") (pinfunction "P$4_P$4") (pintype "bidirectional"))
      (node (ref "MOTOR1") (pin "3") (pinfunction "3_3") (pintype "passive"))
    )
    (net (code "45") (name "/M32") (class "Default")
      (node (ref "MIC4") (pin "P$4") (pinfunction "P$4_P$4") (pintype "bidirectional"))
      (node (ref "MOTOR2") (pin "3") (pinfunction "3_3") (pintype "passive"))
    )
    (net (code "46") (name "/M33") (class "Default")
      (node (ref "MIC9") (pin "P$4") (pinfunction "P$4_P$4") (pintype "bidirectional"))
      (node (ref "MOTOR3") (pin "3") (pinfunction "3_3") (pintype "passive"))
    )
    (net (code "47") (name "/MISO") (class "Default")
      (node (ref "JP1") (pin "27") (pinfunction "27_27") (pintype "passive"))
      (node (ref "JP2") (pin "3") (pinfunction "3_3") (pintype "passive"))
      (node (ref "JP3") (pin "3") (pinfunction "3_3") (pintype "passive"))
      (node (ref "JP4") (pin "3") (pinfunction "3_3") (pintype "passive"))
    )
    (net (code "48") (name "/MISO1") (class "Default")
      (node (ref "IC1") (pin "22") (pinfunction "(MISO/PCINT3)PB3_22") (pintype "bidirectional"))
      (node (ref "JP2") (pin "4") (pinfunction "4_4") (pintype "passive"))
    )
    (net (code "49") (name "/MISO2") (class "Default")
      (node (ref "IC2") (pin "22") (pinfunction "(MISO/PCINT3)PB3_22") (pintype "bidirectional"))
      (node (ref "JP3") (pin "4") (pinfunction "4_4") (pintype "passive"))
    )
    (net (code "50") (name "/MISO3") (class "Default")
      (node (ref "IC3") (pin "22") (pinfunction "(MISO/PCINT3)PB3_22") (pintype "bidirectional"))
      (node (ref "JP4") (pin "4") (pinfunction "4_4") (pintype "passive"))
    )
    (net (code "51") (name "/MOSI") (class "Default")
      (node (ref "JP1") (pin "29") (pinfunction "29_29") (pintype "passive"))
      (node (ref "JP2") (pin "1") (pinfunction "1_1") (pintype "passive"))
      (node (ref "JP3") (pin "1") (pinfunction "1_1") (pintype "passive"))
      (node (ref "JP4") (pin "1") (pinfunction "1_1") (pintype "passive"))
    )
    (net (code "52") (name "/MOSI1") (class "Default")
      (node (ref "IC1") (pin "21") (pinfunction "(MOSI/PCINT2)PB2_21") (pintype "bidirectional"))
      (node (ref "JP2") (pin "2") (pinfunction "2_2") (pintype "passive"))
    )
    (net (code "53") (name "/MOSI2") (class "Default")
      (node (ref "IC2") (pin "21") (pinfunction "(MOSI/PCINT2)PB2_21") (pintype "bidirectional"))
      (node (ref "JP3") (pin "2") (pinfunction "2_2") (pintype "passive"))
    )
    (net (code "54") (name "/MOSI3") (class "Default")
      (node (ref "IC3") (pin "21") (pinfunction "(MOSI/PCINT2)PB2_21") (pintype "bidirectional"))
      (node (ref "JP4") (pin "2") (pinfunction "2_2") (pintype "passive"))
    )
    (net (code "55") (name "/RST1") (class "Default")
      (node (ref "IC1") (pin "30") (pinfunction "RESET_30") (pintype "input"))
      (node (ref "JP1") (pin "25") (pinfunction "25_25") (pintype "passive"))
      (node (ref "R7") (pin "1") (pinfunction "1_1") (pintype "passive"))
      (node (ref "S2") (pin "1") (pinfunction "1_1") (pintype "passive"))
    )
    (net (code "56") (name "/RST2") (class "Default")
      (node (ref "IC2") (pin "30") (pinfunction "RESET_30") (pintype "input"))
      (node (ref "JP1") (pin "23") (pinfunction "23_23") (pintype "passive"))
      (node (ref "R8") (pin "1") (pinfunction "1_1") (pintype "passive"))
      (node (ref "S3") (pin "1") (pinfunction "1_1") (pintype "passive"))
    )
    (net (code "57") (name "/RST3") (class "Default")
      (node (ref "IC3") (pin "30") (pinfunction "RESET_30") (pintype "input"))
      (node (ref "JP1") (pin "5") (pinfunction "5_5") (pintype "passive"))
      (node (ref "R9") (pin "1") (pinfunction "1_1") (pintype "passive"))
      (node (ref "S4") (pin "1") (pinfunction "1_1") (pintype "passive"))
    )
    (net (code "58") (name "/RX1") (class "Default")
      (node (ref "IC1") (pin "2") (pinfunction "(RXD0/PCIN8)PE0_2") (pintype "bidirectional"))
      (node (ref "JP1") (pin "10") (pinfunction "10_10") (pintype "passive"))
    )
    (net (code "59") (name "/RX2") (class "Default")
      (node (ref "IC2") (pin "2") (pinfunction "(RXD0/PCIN8)PE0_2") (pintype "bidirectional"))
      (node (ref "JP1") (pin "12") (pinfunction "12_12") (pintype "passive"))
    )
    (net (code "60") (name "/RX3") (class "Default")
      (node (ref "IC3") (pin "2") (pinfunction "(RXD0/PCIN8)PE0_2") (pintype "bidirectional"))
      (node (ref "JP1") (pin "1") (pinfunction "1_1") (pintype "passive"))
    )
    (net (code "61") (name "/S11") (class "Default")
      (node (ref "IC1") (pin "1") (pinfunction "(OC0B)PG5_1") (pintype "bidirectional"))
      (node (ref "MIC3") (pin "P$2") (pinfunction "P$2_P$2") (pintype "bidirectional"))
    )
    (net (code "62") (name "/S12") (class "Default")
      (node (ref "IC2") (pin "1") (pinfunction "(OC0B)PG5_1") (pintype "bidirectional"))
      (node (ref "MIC6") (pin "P$2") (pinfunction "P$2_P$2") (pintype "bidirectional"))
    )
    (net (code "63") (name "/S13") (class "Default")
      (node (ref "IC3") (pin "1") (pinfunction "(OC0B)PG5_1") (pintype "bidirectional"))
      (node (ref "MIC7") (pin "P$2") (pinfunction "P$2_P$2") (pintype "bidirectional"))
    )
    (net (code "64") (name "/S21") (class "Default")
      (node (ref "IC1") (pin "5") (pinfunction "(OC3A/AIN1)PE3_5") (pintype "bidirectional"))
      (node (ref "MIC3") (pin "P$5") (pinfunction "P$5_P$5") (pintype "bidirectional"))
    )
    (net (code "65") (name "/S22") (class "Default")
      (node (ref "IC2") (pin "5") (pinfunction "(OC3A/AIN1)PE3_5") (pintype "bidirectional"))
      (node (ref "MIC6") (pin "P$5") (pinfunction "P$5_P$5") (pintype "bidirectional"))
    )
    (net (code "66") (name "/S23") (class "Default")
      (node (ref "IC3") (pin "5") (pinfunction "(OC3A/AIN1)PE3_5") (pintype "bidirectional"))
      (node (ref "MIC7") (pin "P$5") (pinfunction "P$5_P$5") (pintype "bidirectional"))
    )
    (net (code "67") (name "/S31") (class "Default")
      (node (ref "IC1") (pin "15") (pinfunction "PH3(OC4A)_15") (pintype "bidirectional"))
      (node (ref "MIC2") (pin "P$2") (pinfunction "P$2_P$2") (pintype "bidirectional"))
    )
    (net (code "68") (name "/S32") (class "Default")
      (node (ref "IC2") (pin "15") (pinfunction "PH3(OC4A)_15") (pintype "bidirectional"))
      (node (ref "MIC5") (pin "P$2") (pinfunction "P$2_P$2") (pintype "bidirectional"))
    )
    (net (code "69") (name "/S33") (class "Default")
      (node (ref "IC3") (pin "15") (pinfunction "PH3(OC4A)_15") (pintype "bidirectional"))
      (node (ref "MIC8") (pin "P$2") (pinfunction "P$2_P$2") (pintype "bidirectional"))
    )
    (net (code "70") (name "/S41") (class "Default")
      (node (ref "IC1") (pin "16") (pinfunction "PH4(OC4B)_16") (pintype "bidirectional"))
      (node (ref "MIC2") (pin "P$5") (pinfunction "P$5_P$5") (pintype "bidirectional"))
    )
    (net (code "71") (name "/S42") (class "Default")
      (node (ref "IC2") (pin "16") (pinfunction "PH4(OC4B)_16") (pintype "bidirectional"))
      (node (ref "MIC5") (pin "P$5") (pinfunction "P$5_P$5") (pintype "bidirectional"))
    )
    (net (code "72") (name "/S43") (class "Default")
      (node (ref "IC3") (pin "16") (pinfunction "PH4(OC4B)_16") (pintype "bidirectional"))
      (node (ref "MIC8") (pin "P$5") (pinfunction "P$5_P$5") (pintype "bidirectional"))
    )
    (net (code "73") (name "/S51") (class "Default")
      (node (ref "IC1") (pin "17") (pinfunction "PH5(OC4C)_17") (pintype "bidirectional"))
      (node (ref "MIC1") (pin "P$2") (pinfunction "P$2_P$2") (pintype "bidirectional"))
    )
    (net (code "74") (name "/S52") (class "Default")
      (node (ref "IC2") (pin "17") (pinfunction "PH5(OC4C)_17") (pintype "bidirectional"))
      (node (ref "MIC4") (pin "P$2") (pinfunction "P$2_P$2") (pintype "bidirectional"))
    )
    (net (code "75") (name "/S53") (class "Default")
      (node (ref "IC3") (pin "17") (pinfunction "PH5(OC4C)_17") (pintype "bidirectional"))
      (node (ref "MIC9") (pin "P$2") (pinfunction "P$2_P$2") (pintype "bidirectional"))
    )
    (net (code "76") (name "/S61") (class "Default")
      (node (ref "IC1") (pin "18") (pinfunction "PH6(OC2B)_18") (pintype "bidirectional"))
      (node (ref "MIC1") (pin "P$5") (pinfunction "P$5_P$5") (pintype "bidirectional"))
    )
    (net (code "77") (name "/S62") (class "Default")
      (node (ref "IC2") (pin "18") (pinfunction "PH6(OC2B)_18") (pintype "bidirectional"))
      (node (ref "MIC4") (pin "P$5") (pinfunction "P$5_P$5") (pintype "bidirectional"))
    )
    (net (code "78") (name "/S63") (class "Default")
      (node (ref "IC3") (pin "18") (pinfunction "PH6(OC2B)_18") (pintype "bidirectional"))
      (node (ref "MIC9") (pin "P$5") (pinfunction "P$5_P$5") (pintype "bidirectional"))
    )
    (net (code "79") (name "/SS1") (class "Default")
      (node (ref "IC1") (pin "19") (pinfunction "(SS/PCINT0)PB0_19") (pintype "bidirectional"))
      (node (ref "JP1") (pin "30") (pinfunction "30_30") (pintype "passive"))
    )
    (net (code "80") (name "/SS2") (class "Default")
      (node (ref "IC2") (pin "19") (pinfunction "(SS/PCINT0)PB0_19") (pintype "bidirectional"))
      (node (ref "JP1") (pin "19") (pinfunction "19_19") (pintype "passive"))
    )
    (net (code "81") (name "/SS3") (class "Default")
      (node (ref "IC3") (pin "19") (pinfunction "(SS/PCINT0)PB0_19") (pintype "bidirectional"))
      (node (ref "JP1") (pin "17") (pinfunction "17_17") (pintype "passive"))
    )
    (net (code "82") (name "/TX1") (class "Default")
      (node (ref "IC1") (pin "3") (pinfunction "(TXD0)PE1_3") (pintype "bidirectional"))
      (node (ref "JP1") (pin "11") (pinfunction "11_11") (pintype "passive"))
    )
    (net (code "83") (name "/TX2") (class "Default")
      (node (ref "IC2") (pin "3") (pinfunction "(TXD0)PE1_3") (pintype "bidirectional"))
      (node (ref "JP1") (pin "9") (pinfunction "9_9") (pintype "passive"))
    )
    (net (code "84") (name "/TX3") (class "Default")
      (node (ref "IC3") (pin "3") (pinfunction "(TXD0)PE1_3") (pintype "bidirectional"))
      (node (ref "JP1") (pin "3") (pinfunction "3_3") (pintype "passive"))
    )
    (net (code "85") (name "Net-(C9-Pad1)") (class "Default")
      (node (ref "C9") (pin "1") (pinfunction "1_1") (pintype "passive"))
      (node (ref "S3") (pin "2") (pinfunction "2_2") (pintype "passive"))
    )
    (net (code "86") (name "Net-(C10-Pad1)") (class "Default")
      (node (ref "C10") (pin "1") (pinfunction "1_1") (pintype "passive"))
      (node (ref "S2") (pin "2") (pinfunction "2_2") (pintype "passive"))
    )
    (net (code "87") (name "Net-(C11-Pad1)") (class "Default")
      (node (ref "C11") (pin "1") (pinfunction "1_1") (pintype "passive"))
      (node (ref "S4") (pin "2") (pinfunction "2_2") (pintype "passive"))
    )
    (net (code "88") (name "Net-(D2-PadC)") (class "Default")
      (node (ref "D2") (pin "C") (pinfunction "C_C") (pintype "passive"))
      (node (ref "R3") (pin "1") (pinfunction "1_1") (pintype "passive"))
    )
    (net (code "89") (name "Net-(D3-PadC)") (class "Default")
      (node (ref "D3") (pin "C") (pinfunction "C_C") (pintype "passive"))
      (node (ref "R4") (pin "1") (pinfunction "1_1") (pintype "passive"))
    )
    (net (code "90") (name "Net-(D7-PadC)") (class "Default")
      (node (ref "D7") (pin "C") (pinfunction "C_C") (pintype "passive"))
      (node (ref "R10") (pin "1") (pinfunction "1_1") (pintype "passive"))
    )
    (net (code "91") (name "Net-(D8-PadC)") (class "Default")
      (node (ref "D8") (pin "C") (pinfunction "C_C") (pintype "passive"))
      (node (ref "R11") (pin "1") (pinfunction "1_1") (pintype "passive"))
    )
    (net (code "92") (name "Net-(D9-PadC)") (class "Default")
      (node (ref "D9") (pin "C") (pinfunction "C_C") (pintype "passive"))
      (node (ref "R12") (pin "1") (pinfunction "1_1") (pintype "passive"))
    )
    (net (code "93") (name "Net-(D11-PadC)") (class "Default")
      (node (ref "D11") (pin "C") (pinfunction "C_C") (pintype "passive"))
      (node (ref "R14") (pin "1") (pinfunction "1_1") (pintype "passive"))
    )
    (net (code "94") (name "Net-(D12-PadC)") (class "Default")
      (node (ref "D12") (pin "C") (pinfunction "C_C") (pintype "passive"))
      (node (ref "R15") (pin "1") (pinfunction "1_1") (pintype "passive"))
    )
    (net (code "95") (name "Net-(D13-PadC)") (class "Default")
      (node (ref "D13") (pin "C") (pinfunction "C_C") (pintype "passive"))
      (node (ref "R16") (pin "1") (pinfunction "1_1") (pintype "passive"))
    )
    (net (code "96") (name "Net-(D15-PadC)") (class "Default")
      (node (ref "D15") (pin "C") (pinfunction "C_C") (pintype "passive"))
      (node (ref "R18") (pin "1") (pinfunction "1_1") (pintype "passive"))
    )
    (net (code "97") (name "Net-(D16-PadC)") (class "Default")
      (node (ref "D16") (pin "C") (pinfunction "C_C") (pintype "passive"))
      (node (ref "R19") (pin "1") (pinfunction "1_1") (pintype "passive"))
    )
    (net (code "98") (name "Net-(D17-PadC)") (class "Default")
      (node (ref "D17") (pin "C") (pinfunction "C_C") (pintype "passive"))
      (node (ref "R20") (pin "1") (pinfunction "1_1") (pintype "passive"))
    )
    (net (code "99") (name "Net-(IC1-AREF)") (class "Default")
      (node (ref "C2") (pin "1") (pinfunction "1_1") (pintype "passive"))
      (node (ref "IC1") (pin "98") (pinfunction "AREF_98") (pintype "bidirectional"))
    )
    (net (code "100") (name "Net-(IC1-XTAL1)") (class "Default")
      (node (ref "C18") (pin "2") (pinfunction "2_2") (pintype "passive"))
      (node (ref "IC1") (pin "34") (pinfunction "XTAL1_34") (pintype "input"))
      (node (ref "Y2") (pin "1") (pinfunction "1_1") (pintype "passive"))
    )
    (net (code "101") (name "Net-(IC1-XTAL2)") (class "Default")
      (node (ref "C19") (pin "2") (pinfunction "2_2") (pintype "passive"))
      (node (ref "IC1") (pin "33") (pinfunction "XTAL2_33") (pintype "output"))
      (node (ref "Y2") (pin "3") (pinfunction "2_3") (pintype "passive"))
    )
    (net (code "102") (name "Net-(IC2-AREF)") (class "Default")
      (node (ref "C14") (pin "1") (pinfunction "1_1") (pintype "passive"))
      (node (ref "IC2") (pin "98") (pinfunction "AREF_98") (pintype "bidirectional"))
    )
    (net (code "103") (name "Net-(IC2-XTAL1)") (class "Default")
      (node (ref "C16") (pin "2") (pinfunction "2_2") (pintype "passive"))
      (node (ref "IC2") (pin "34") (pinfunction "XTAL1_34") (pintype "input"))
      (node (ref "Y3") (pin "1") (pinfunction "1_1") (pintype "passive"))
    )
    (net (code "104") (name "Net-(IC2-XTAL2)") (class "Default")
      (node (ref "C17") (pin "2") (pinfunction "2_2") (pintype "passive"))
      (node (ref "IC2") (pin "33") (pinfunction "XTAL2_33") (pintype "output"))
      (node (ref "Y3") (pin "3") (pinfunction "2_3") (pintype "passive"))
    )
    (net (code "105") (name "Net-(IC3-AREF)") (class "Default")
      (node (ref "C3") (pin "1") (pinfunction "1_1") (pintype "passive"))
      (node (ref "IC3") (pin "98") (pinfunction "AREF_98") (pintype "bidirectional"))
    )
    (net (code "106") (name "Net-(IC3-XTAL1)") (class "Default")
      (node (ref "C12") (pin "2") (pinfunction "2_2") (pintype "passive"))
      (node (ref "IC3") (pin "34") (pinfunction "XTAL1_34") (pintype "input"))
      (node (ref "Y4") (pin "1") (pinfunction "1_1") (pintype "passive"))
    )
    (net (code "107") (name "Net-(IC3-XTAL2)") (class "Default")
      (node (ref "C13") (pin "2") (pinfunction "2_2") (pintype "passive"))
      (node (ref "IC3") (pin "33") (pinfunction "XTAL2_33") (pintype "output"))
      (node (ref "Y4") (pin "3") (pinfunction "2_3") (pintype "passive"))
    )
    (net (code "108") (name "Net-(IC4-FILTER)") (class "Default")
      (node (ref "C8") (pin "1") (pinfunction "1_1") (pintype "passive"))
      (node (ref "IC4") (pin "6") (pinfunction "FILTER_6") (pintype "bidirectional"))
    )
    (net (code "109") (name "Net-(IC5-FILTER)") (class "Default")
      (node (ref "C23") (pin "1") (pinfunction "1_1") (pintype "passive"))
      (node (ref "IC5") (pin "6") (pinfunction "FILTER_6") (pintype "bidirectional"))
    )
    (net (code "110") (name "Net-(IC6-FILTER)") (class "Default")
      (node (ref "C24") (pin "1") (pinfunction "1_1") (pintype "passive"))
      (node (ref "IC6") (pin "6") (pinfunction "FILTER_6") (pintype "bidirectional"))
    )
    (net (code "111") (name "unconnected-(FRC1-Pad2)") (class "Default")
      (node (ref "FRC1") (pin "2") (pinfunction "2_2") (pintype "passive"))
    )
    (net (code "112") (name "unconnected-(FRC1-Pad3)") (class "Default")
      (node (ref "FRC1") (pin "3") (pinfunction "3_3") (pintype "passive"))
    )
    (net (code "113") (name "unconnected-(FRC1-Pad6)") (class "Default")
      (node (ref "FRC1") (pin "6") (pinfunction "6_6") (pintype "passive"))
    )
    (net (code "114") (name "unconnected-(FRC1-Pad8)") (class "Default")
      (node (ref "FRC1") (pin "8") (pinfunction "8_8") (pintype "passive"))
    )
    (net (code "115") (name "unconnected-(FRC1-Pad9)") (class "Default")
      (node (ref "FRC1") (pin "9") (pinfunction "9_9") (pintype "passive"))
    )
    (net (code "116") (name "unconnected-(FRC1-Pad10)") (class "Default")
      (node (ref "FRC1") (pin "10") (pinfunction "10_10") (pintype "passive"))
    )
    (net (code "117") (name "unconnected-(FRC2-Pad2)") (class "Default")
      (node (ref "FRC2") (pin "2") (pinfunction "2_2") (pintype "passive"))
    )
    (net (code "118") (name "unconnected-(FRC2-Pad3)") (class "Default")
      (node (ref "FRC2") (pin "3") (pinfunction "3_3") (pintype "passive"))
    )
    (net (code "119") (name "unconnected-(FRC2-Pad6)") (class "Default")
      (node (ref "FRC2") (pin "6") (pinfunction "6_6") (pintype "passive"))
    )
    (net (code "120") (name "unconnected-(FRC2-Pad8)") (class "Default")
      (node (ref "FRC2") (pin "8") (pinfunction "8_8") (pintype "passive"))
    )
    (net (code "121") (name "unconnected-(FRC2-Pad9)") (class "Default")
      (node (ref "FRC2") (pin "9") (pinfunction "9_9") (pintype "passive"))
    )
    (net (code "122") (name "unconnected-(FRC2-Pad10)") (class "Default")
      (node (ref "FRC2") (pin "10") (pinfunction "10_10") (pintype "passive"))
    )
    (net (code "123") (name "unconnected-(FRC3-Pad2)") (class "Default")
      (node (ref "FRC3") (pin "2") (pinfunction "2_2") (pintype "passive"))
    )
    (net (code "124") (name "unconnected-(FRC3-Pad3)") (class "Default")
      (node (ref "FRC3") (pin "3") (pinfunction "3_3") (pintype "passive"))
    )
    (net (code "125") (name "unconnected-(FRC3-Pad6)") (class "Default")
      (node (ref "FRC3") (pin "6") (pinfunction "6_6") (pintype "passive"))
    )
    (net (code "126") (name "unconnected-(FRC3-Pad8)") (class "Default")
      (node (ref "FRC3") (pin "8") (pinfunction "8_8") (pintype "passive"))
    )
    (net (code "127") (name "unconnected-(FRC3-Pad9)") (class "Default")
      (node (ref "FRC3") (pin "9") (pinfunction "9_9") (pintype "passive"))
    )
    (net (code "128") (name "unconnected-(FRC3-Pad10)") (class "Default")
      (node (ref "FRC3") (pin "10") (pinfunction "10_10") (pintype "passive"))
    )
    (net (code "129") (name "unconnected-(IC1-(A8)PC0-Pad53)") (class "Default")
      (node (ref "IC1") (pin "53") (pinfunction "(A8)PC0_53") (pintype "bidirectional"))
    )
    (net (code "130") (name "unconnected-(IC1-(A9)PC1-Pad54)") (class "Default")
      (node (ref "IC1") (pin "54") (pinfunction "(A9)PC1_54") (pintype "bidirectional"))
    )
    (net (code "131") (name "unconnected-(IC1-(A10)PC2-Pad55)") (class "Default")
      (node (ref "IC1") (pin "55") (pinfunction "(A10)PC2_55") (pintype "bidirectional"))
    )
    (net (code "132") (name "unconnected-(IC1-(A11)PC3-Pad56)") (class "Default")
      (node (ref "IC1") (pin "56") (pinfunction "(A11)PC3_56") (pintype "bidirectional"))
    )
    (net (code "133") (name "unconnected-(IC1-(A12)PC4-Pad57)") (class "Default")
      (node (ref "IC1") (pin "57") (pinfunction "(A12)PC4_57") (pintype "bidirectional"))
    )
    (net (code "134") (name "unconnected-(IC1-(A13)PC5-Pad58)") (class "Default")
      (node (ref "IC1") (pin "58") (pinfunction "(A13)PC5_58") (pintype "bidirectional"))
    )
    (net (code "135") (name "unconnected-(IC1-(A14)PC6-Pad59)") (class "Default")
      (node (ref "IC1") (pin "59") (pinfunction "(A14)PC6_59") (pintype "bidirectional"))
    )
    (net (code "136") (name "unconnected-(IC1-(A15)PC7-Pad60)") (class "Default")
      (node (ref "IC1") (pin "60") (pinfunction "(A15)PC7_60") (pintype "bidirectional"))
    )
    (net (code "137") (name "unconnected-(IC1-(AD0)PA0-Pad78)") (class "Default")
      (node (ref "IC1") (pin "78") (pinfunction "(AD0)PA0_78") (pintype "bidirectional"))
    )
    (net (code "138") (name "unconnected-(IC1-(AD1)PA1-Pad77)") (class "Default")
      (node (ref "IC1") (pin "77") (pinfunction "(AD1)PA1_77") (pintype "bidirectional"))
    )
    (net (code "139") (name "unconnected-(IC1-(AD2)PA2-Pad76)") (class "Default")
      (node (ref "IC1") (pin "76") (pinfunction "(AD2)PA2_76") (pintype "bidirectional"))
    )
    (net (code "140") (name "unconnected-(IC1-(AD3)PA3-Pad75)") (class "Default")
      (node (ref "IC1") (pin "75") (pinfunction "(AD3)PA3_75") (pintype "bidirectional"))
    )
    (net (code "141") (name "unconnected-(IC1-(AD4)PA4-Pad74)") (class "Default")
      (node (ref "IC1") (pin "74") (pinfunction "(AD4)PA4_74") (pintype "bidirectional"))
    )
    (net (code "142") (name "unconnected-(IC1-(AD5)PA5-Pad73)") (class "Default")
      (node (ref "IC1") (pin "73") (pinfunction "(AD5)PA5_73") (pintype "bidirectional"))
    )
    (net (code "143") (name "unconnected-(IC1-(AD6)PA6-Pad72)") (class "Default")
      (node (ref "IC1") (pin "72") (pinfunction "(AD6)PA6_72") (pintype "bidirectional"))
    )
    (net (code "144") (name "unconnected-(IC1-(AD7)PA7-Pad71)") (class "Default")
      (node (ref "IC1") (pin "71") (pinfunction "(AD7)PA7_71") (pintype "bidirectional"))
    )
    (net (code "145") (name "unconnected-(IC1-(ADC1)PF1-Pad96)") (class "Default")
      (node (ref "IC1") (pin "96") (pinfunction "(ADC1)PF1_96") (pintype "bidirectional"))
    )
    (net (code "146") (name "unconnected-(IC1-(ADC2)PF2-Pad95)") (class "Default")
      (node (ref "IC1") (pin "95") (pinfunction "(ADC2)PF2_95") (pintype "bidirectional"))
    )
    (net (code "147") (name "unconnected-(IC1-(ADC3)PF3-Pad94)") (class "Default")
      (node (ref "IC1") (pin "94") (pinfunction "(ADC3)PF3_94") (pintype "bidirectional"))
    )
    (net (code "148") (name "unconnected-(IC1-(ADC4{slash}TCK)PF4-Pad93)") (class "Default")
      (node (ref "IC1") (pin "93") (pinfunction "(ADC4/TCK)PF4_93") (pintype "bidirectional"))
    )
    (net (code "149") (name "unconnected-(IC1-(ADC5{slash}TMS)PF5-Pad92)") (class "Default")
      (node (ref "IC1") (pin "92") (pinfunction "(ADC5/TMS)PF5_92") (pintype "bidirectional"))
    )
    (net (code "150") (name "unconnected-(IC1-(ADC6{slash}TDO)PF6-Pad91)") (class "Default")
      (node (ref "IC1") (pin "91") (pinfunction "(ADC6/TDO)PF6_91") (pintype "bidirectional"))
    )
    (net (code "151") (name "unconnected-(IC1-(ADC7{slash}TDI)PF7-Pad90)") (class "Default")
      (node (ref "IC1") (pin "90") (pinfunction "(ADC7/TDI)PF7_90") (pintype "bidirectional"))
    )
    (net (code "152") (name "unconnected-(IC1-(ALE)PG2-Pad70)") (class "Default")
      (node (ref "IC1") (pin "70") (pinfunction "(ALE)PG2_70") (pintype "bidirectional"))
    )
    (net (code "153") (name "unconnected-(IC1-(CLKO{slash}ICP3{slash}INT7)PE7-Pad9)") (class "Default")
      (node (ref "IC1") (pin "9") (pinfunction "(CLKO/ICP3/INT7)PE7_9") (pintype "bidirectional"))
    )
    (net (code "154") (name "unconnected-(IC1-(ICP1)PD4-Pad47)") (class "Default")
      (node (ref "IC1") (pin "47") (pinfunction "(ICP1)PD4_47") (pintype "bidirectional"))
    )
    (net (code "155") (name "unconnected-(IC1-(OC0A{slash}OC1C{slash}PCINT7)PB7-Pad26)") (class "Default")
      (node (ref "IC1") (pin "26") (pinfunction "(OC0A/OC1C/PCINT7)PB7_26") (pintype "bidirectional"))
    )
    (net (code "156") (name "unconnected-(IC1-(OC3B{slash}INT4)PE4-Pad6)") (class "Default")
      (node (ref "IC1") (pin "6") (pinfunction "(OC3B/INT4)PE4_6") (pintype "bidirectional"))
    )
    (net (code "157") (name "unconnected-(IC1-(RD)PG1-Pad52)") (class "Default")
      (node (ref "IC1") (pin "52") (pinfunction "(RD)PG1_52") (pintype "bidirectional"))
    )
    (net (code "158") (name "unconnected-(IC1-(T0)PD7-Pad50)") (class "Default")
      (node (ref "IC1") (pin "50") (pinfunction "(T0)PD7_50") (pintype "bidirectional"))
    )
    (net (code "159") (name "unconnected-(IC1-(T1)PD6-Pad49)") (class "Default")
      (node (ref "IC1") (pin "49") (pinfunction "(T1)PD6_49") (pintype "bidirectional"))
    )
    (net (code "160") (name "unconnected-(IC1-(T3{slash}INT6)PE6-Pad8)") (class "Default")
      (node (ref "IC1") (pin "8") (pinfunction "(T3/INT6)PE6_8") (pintype "bidirectional"))
    )
    (net (code "161") (name "unconnected-(IC1-(TOSC1)PG4-Pad29)") (class "Default")
      (node (ref "IC1") (pin "29") (pinfunction "(TOSC1)PG4_29") (pintype "bidirectional"))
    )
    (net (code "162") (name "unconnected-(IC1-(TOSC2)PG3-Pad28)") (class "Default")
      (node (ref "IC1") (pin "28") (pinfunction "(TOSC2)PG3_28") (pintype "bidirectional"))
    )
    (net (code "163") (name "unconnected-(IC1-(WR)PG0-Pad51)") (class "Default")
      (node (ref "IC1") (pin "51") (pinfunction "(WR)PG0_51") (pintype "bidirectional"))
    )
    (net (code "164") (name "unconnected-(IC1-(XCK0{slash}AIN0)PE2-Pad4)") (class "Default")
      (node (ref "IC1") (pin "4") (pinfunction "(XCK0/AIN0)PE2_4") (pintype "bidirectional"))
    )
    (net (code "165") (name "unconnected-(IC1-(XCK1)PD5-Pad48)") (class "Default")
      (node (ref "IC1") (pin "48") (pinfunction "(XCK1)PD5_48") (pintype "bidirectional"))
    )
    (net (code "166") (name "unconnected-(IC1-PH0(RXD2)-Pad12)") (class "Default")
      (node (ref "IC1") (pin "12") (pinfunction "PH0(RXD2)_12") (pintype "bidirectional"))
    )
    (net (code "167") (name "unconnected-(IC1-PH1(TXD2)-Pad13)") (class "Default")
      (node (ref "IC1") (pin "13") (pinfunction "PH1(TXD2)_13") (pintype "bidirectional"))
    )
    (net (code "168") (name "unconnected-(IC1-PH2(XCK2)-Pad14)") (class "Default")
      (node (ref "IC1") (pin "14") (pinfunction "PH2(XCK2)_14") (pintype "bidirectional"))
    )
    (net (code "169") (name "unconnected-(IC1-PH7(T4)-Pad27)") (class "Default")
      (node (ref "IC1") (pin "27") (pinfunction "PH7(T4)_27") (pintype "bidirectional"))
    )
    (net (code "170") (name "unconnected-(IC1-PJ0(RXD3{slash}PCINT9)-Pad63)") (class "Default")
      (node (ref "IC1") (pin "63") (pinfunction "PJ0(RXD3/PCINT9)_63") (pintype "bidirectional"))
    )
    (net (code "171") (name "unconnected-(IC1-PJ1(TXD3{slash}PCINT10)-Pad64)") (class "Default")
      (node (ref "IC1") (pin "64") (pinfunction "PJ1(TXD3/PCINT10)_64") (pintype "bidirectional"))
    )
    (net (code "172") (name "unconnected-(IC1-PJ2(XCK3{slash}PCINT11)-Pad65)") (class "Default")
      (node (ref "IC1") (pin "65") (pinfunction "PJ2(XCK3/PCINT11)_65") (pintype "bidirectional"))
    )
    (net (code "173") (name "unconnected-(IC1-PJ3(PCINT12)-Pad66)") (class "Default")
      (node (ref "IC1") (pin "66") (pinfunction "PJ3(PCINT12)_66") (pintype "bidirectional"))
    )
    (net (code "174") (name "unconnected-(IC1-PJ4(PCINT13)-Pad67)") (class "Default")
      (node (ref "IC1") (pin "67") (pinfunction "PJ4(PCINT13)_67") (pintype "bidirectional"))
    )
    (net (code "175") (name "unconnected-(IC1-PJ5(PCINT14)-Pad68)") (class "Default")
      (node (ref "IC1") (pin "68") (pinfunction "PJ5(PCINT14)_68") (pintype "bidirectional"))
    )
    (net (code "176") (name "unconnected-(IC1-PJ6(PCINT15)-Pad69)") (class "Default")
      (node (ref "IC1") (pin "69") (pinfunction "PJ6(PCINT15)_69") (pintype "bidirectional"))
    )
    (net (code "177") (name "unconnected-(IC1-PJ7-Pad79)") (class "Default")
      (node (ref "IC1") (pin "79") (pinfunction "PJ7_79") (pintype "bidirectional"))
    )
    (net (code "178") (name "unconnected-(IC1-PK0(ADC8{slash}PCINT16)-Pad89)") (class "Default")
      (node (ref "IC1") (pin "89") (pinfunction "PK0(ADC8/PCINT16)_89") (pintype "bidirectional"))
    )
    (net (code "179") (name "unconnected-(IC1-PK1(ADC9{slash}PCINT17)-Pad88)") (class "Default")
      (node (ref "IC1") (pin "88") (pinfunction "PK1(ADC9/PCINT17)_88") (pintype "bidirectional"))
    )
    (net (code "180") (name "unconnected-(IC1-PK2(ADC10{slash}PCINT18)-Pad87)") (class "Default")
      (node (ref "IC1") (pin "87") (pinfunction "PK2(ADC10/PCINT18)_87") (pintype "bidirectional"))
    )
    (net (code "181") (name "unconnected-(IC1-PK3(ADC11{slash}PCINT19)-Pad86)") (class "Default")
      (node (ref "IC1") (pin "86") (pinfunction "PK3(ADC11/PCINT19)_86") (pintype "bidirectional"))
    )
    (net (code "182") (name "unconnected-(IC1-PK4(ADC12{slash}PCINT20)-Pad85)") (class "Default")
      (node (ref "IC1") (pin "85") (pinfunction "PK4(ADC12/PCINT20)_85") (pintype "bidirectional"))
    )
    (net (code "183") (name "unconnected-(IC1-PK5(ADC13{slash}PCINT21)-Pad84)") (class "Default")
      (node (ref "IC1") (pin "84") (pinfunction "PK5(ADC13/PCINT21)_84") (pintype "bidirectional"))
    )
    (net (code "184") (name "unconnected-(IC1-PK6(ADC14{slash}PCINT22)-Pad83)") (class "Default")
      (node (ref "IC1") (pin "83") (pinfunction "PK6(ADC14/PCINT22)_83") (pintype "bidirectional"))
    )
    (net (code "185") (name "unconnected-(IC1-PK7(ADC15{slash}PCINT23)-Pad82)") (class "Default")
      (node (ref "IC1") (pin "82") (pinfunction "PK7(ADC15/PCINT23)_82") (pintype "bidirectional"))
    )
    (net (code "186") (name "unconnected-(IC1-PL0(ICP4)-Pad35)") (class "Default")
      (node (ref "IC1") (pin "35") (pinfunction "PL0(ICP4)_35") (pintype "bidirectional"))
    )
    (net (code "187") (name "unconnected-(IC1-PL1(ICP5)-Pad36)") (class "Default")
      (node (ref "IC1") (pin "36") (pinfunction "PL1(ICP5)_36") (pintype "bidirectional"))
    )
    (net (code "188") (name "unconnected-(IC1-PL2(T5)-Pad37)") (class "Default")
      (node (ref "IC1") (pin "37") (pinfunction "PL2(T5)_37") (pintype "bidirectional"))
    )
    (net (code "189") (name "unconnected-(IC1-PL3(OC5A)-Pad38)") (class "Default")
      (node (ref "IC1") (pin "38") (pinfunction "PL3(OC5A)_38") (pintype "bidirectional"))
    )
    (net (code "190") (name "unconnected-(IC1-PL4(OC5B)-Pad39)") (class "Default")
      (node (ref "IC1") (pin "39") (pinfunction "PL4(OC5B)_39") (pintype "bidirectional"))
    )
    (net (code "191") (name "unconnected-(IC1-PL5(OC5C)-Pad40)") (class "Default")
      (node (ref "IC1") (pin "40") (pinfunction "PL5(OC5C)_40") (pintype "bidirectional"))
    )
    (net (code "192") (name "unconnected-(IC1-PL6-Pad41)") (class "Default")
      (node (ref "IC1") (pin "41") (pinfunction "PL6_41") (pintype "bidirectional"))
    )
    (net (code "193") (name "unconnected-(IC1-PL7-Pad42)") (class "Default")
      (node (ref "IC1") (pin "42") (pinfunction "PL7_42") (pintype "bidirectional"))
    )
    (net (code "194") (name "unconnected-(IC2-(A8)PC0-Pad53)") (class "Default")
      (node (ref "IC2") (pin "53") (pinfunction "(A8)PC0_53") (pintype "bidirectional"))
    )
    (net (code "195") (name "unconnected-(IC2-(A9)PC1-Pad54)") (class "Default")
      (node (ref "IC2") (pin "54") (pinfunction "(A9)PC1_54") (pintype "bidirectional"))
    )
    (net (code "196") (name "unconnected-(IC2-(A10)PC2-Pad55)") (class "Default")
      (node (ref "IC2") (pin "55") (pinfunction "(A10)PC2_55") (pintype "bidirectional"))
    )
    (net (code "197") (name "unconnected-(IC2-(A11)PC3-Pad56)") (class "Default")
      (node (ref "IC2") (pin "56") (pinfunction "(A11)PC3_56") (pintype "bidirectional"))
    )
    (net (code "198") (name "unconnected-(IC2-(A12)PC4-Pad57)") (class "Default")
      (node (ref "IC2") (pin "57") (pinfunction "(A12)PC4_57") (pintype "bidirectional"))
    )
    (net (code "199") (name "unconnected-(IC2-(A13)PC5-Pad58)") (class "Default")
      (node (ref "IC2") (pin "58") (pinfunction "(A13)PC5_58") (pintype "bidirectional"))
    )
    (net (code "200") (name "unconnected-(IC2-(A14)PC6-Pad59)") (class "Default")
      (node (ref "IC2") (pin "59") (pinfunction "(A14)PC6_59") (pintype "bidirectional"))
    )
    (net (code "201") (name "unconnected-(IC2-(A15)PC7-Pad60)") (class "Default")
      (node (ref "IC2") (pin "60") (pinfunction "(A15)PC7_60") (pintype "bidirectional"))
    )
    (net (code "202") (name "unconnected-(IC2-(AD0)PA0-Pad78)") (class "Default")
      (node (ref "IC2") (pin "78") (pinfunction "(AD0)PA0_78") (pintype "bidirectional"))
    )
    (net (code "203") (name "unconnected-(IC2-(AD1)PA1-Pad77)") (class "Default")
      (node (ref "IC2") (pin "77") (pinfunction "(AD1)PA1_77") (pintype "bidirectional"))
    )
    (net (code "204") (name "unconnected-(IC2-(AD2)PA2-Pad76)") (class "Default")
      (node (ref "IC2") (pin "76") (pinfunction "(AD2)PA2_76") (pintype "bidirectional"))
    )
    (net (code "205") (name "unconnected-(IC2-(AD3)PA3-Pad75)") (class "Default")
      (node (ref "IC2") (pin "75") (pinfunction "(AD3)PA3_75") (pintype "bidirectional"))
    )
    (net (code "206") (name "unconnected-(IC2-(AD4)PA4-Pad74)") (class "Default")
      (node (ref "IC2") (pin "74") (pinfunction "(AD4)PA4_74") (pintype "bidirectional"))
    )
    (net (code "207") (name "unconnected-(IC2-(AD5)PA5-Pad73)") (class "Default")
      (node (ref "IC2") (pin "73") (pinfunction "(AD5)PA5_73") (pintype "bidirectional"))
    )
    (net (code "208") (name "unconnected-(IC2-(AD6)PA6-Pad72)") (class "Default")
      (node (ref "IC2") (pin "72") (pinfunction "(AD6)PA6_72") (pintype "bidirectional"))
    )
    (net (code "209") (name "unconnected-(IC2-(AD7)PA7-Pad71)") (class "Default")
      (node (ref "IC2") (pin "71") (pinfunction "(AD7)PA7_71") (pintype "bidirectional"))
    )
    (net (code "210") (name "unconnected-(IC2-(ADC1)PF1-Pad96)") (class "Default")
      (node (ref "IC2") (pin "96") (pinfunction "(ADC1)PF1_96") (pintype "bidirectional"))
    )
    (net (code "211") (name "unconnected-(IC2-(ADC2)PF2-Pad95)") (class "Default")
      (node (ref "IC2") (pin "95") (pinfunction "(ADC2)PF2_95") (pintype "bidirectional"))
    )
    (net (code "212") (name "unconnected-(IC2-(ADC3)PF3-Pad94)") (class "Default")
      (node (ref "IC2") (pin "94") (pinfunction "(ADC3)PF3_94") (pintype "bidirectional"))
    )
    (net (code "213") (name "unconnected-(IC2-(ADC4{slash}TCK)PF4-Pad93)") (class "Default")
      (node (ref "IC2") (pin "93") (pinfunction "(ADC4/TCK)PF4_93") (pintype "bidirectional"))
    )
    (net (code "214") (name "unconnected-(IC2-(ADC5{slash}TMS)PF5-Pad92)") (class "Default")
      (node (ref "IC2") (pin "92") (pinfunction "(ADC5/TMS)PF5_92") (pintype "bidirectional"))
    )
    (net (code "215") (name "unconnected-(IC2-(ADC6{slash}TDO)PF6-Pad91)") (class "Default")
      (node (ref "IC2") (pin "91") (pinfunction "(ADC6/TDO)PF6_91") (pintype "bidirectional"))
    )
    (net (code "216") (name "unconnected-(IC2-(ADC7{slash}TDI)PF7-Pad90)") (class "Default")
      (node (ref "IC2") (pin "90") (pinfunction "(ADC7/TDI)PF7_90") (pintype "bidirectional"))
    )
    (net (code "217") (name "unconnected-(IC2-(ALE)PG2-Pad70)") (class "Default")
      (node (ref "IC2") (pin "70") (pinfunction "(ALE)PG2_70") (pintype "bidirectional"))
    )
    (net (code "218") (name "unconnected-(IC2-(CLKO{slash}ICP3{slash}INT7)PE7-Pad9)") (class "Default")
      (node (ref "IC2") (pin "9") (pinfunction "(CLKO/ICP3/INT7)PE7_9") (pintype "bidirectional"))
    )
    (net (code "219") (name "unconnected-(IC2-(ICP1)PD4-Pad47)") (class "Default")
      (node (ref "IC2") (pin "47") (pinfunction "(ICP1)PD4_47") (pintype "bidirectional"))
    )
    (net (code "220") (name "unconnected-(IC2-(OC0A{slash}OC1C{slash}PCINT7)PB7-Pad26)") (class "Default")
      (node (ref "IC2") (pin "26") (pinfunction "(OC0A/OC1C/PCINT7)PB7_26") (pintype "bidirectional"))
    )
    (net (code "221") (name "unconnected-(IC2-(OC3B{slash}INT4)PE4-Pad6)") (class "Default")
      (node (ref "IC2") (pin "6") (pinfunction "(OC3B/INT4)PE4_6") (pintype "bidirectional"))
    )
    (net (code "222") (name "unconnected-(IC2-(RD)PG1-Pad52)") (class "Default")
      (node (ref "IC2") (pin "52") (pinfunction "(RD)PG1_52") (pintype "bidirectional"))
    )
    (net (code "223") (name "unconnected-(IC2-(T0)PD7-Pad50)") (class "Default")
      (node (ref "IC2") (pin "50") (pinfunction "(T0)PD7_50") (pintype "bidirectional"))
    )
    (net (code "224") (name "unconnected-(IC2-(T1)PD6-Pad49)") (class "Default")
      (node (ref "IC2") (pin "49") (pinfunction "(T1)PD6_49") (pintype "bidirectional"))
    )
    (net (code "225") (name "unconnected-(IC2-(T3{slash}INT6)PE6-Pad8)") (class "Default")
      (node (ref "IC2") (pin "8") (pinfunction "(T3/INT6)PE6_8") (pintype "bidirectional"))
    )
    (net (code "226") (name "unconnected-(IC2-(TOSC1)PG4-Pad29)") (class "Default")
      (node (ref "IC2") (pin "29") (pinfunction "(TOSC1)PG4_29") (pintype "bidirectional"))
    )
    (net (code "227") (name "unconnected-(IC2-(TOSC2)PG3-Pad28)") (class "Default")
      (node (ref "IC2") (pin "28") (pinfunction "(TOSC2)PG3_28") (pintype "bidirectional"))
    )
    (net (code "228") (name "unconnected-(IC2-(WR)PG0-Pad51)") (class "Default")
      (node (ref "IC2") (pin "51") (pinfunction "(WR)PG0_51") (pintype "bidirectional"))
    )
    (net (code "229") (name "unconnected-(IC2-(XCK0{slash}AIN0)PE2-Pad4)") (class "Default")
      (node (ref "IC2") (pin "4") (pinfunction "(XCK0/AIN0)PE2_4") (pintype "bidirectional"))
    )
    (net (code "230") (name "unconnected-(IC2-(XCK1)PD5-Pad48)") (class "Default")
      (node (ref "IC2") (pin "48") (pinfunction "(XCK1)PD5_48") (pintype "bidirectional"))
    )
    (net (code "231") (name "unconnected-(IC2-PH0(RXD2)-Pad12)") (class "Default")
      (node (ref "IC2") (pin "12") (pinfunction "PH0(RXD2)_12") (pintype "bidirectional"))
    )
    (net (code "232") (name "unconnected-(IC2-PH1(TXD2)-Pad13)") (class "Default")
      (node (ref "IC2") (pin "13") (pinfunction "PH1(TXD2)_13") (pintype "bidirectional"))
    )
    (net (code "233") (name "unconnected-(IC2-PH2(XCK2)-Pad14)") (class "Default")
      (node (ref "IC2") (pin "14") (pinfunction "PH2(XCK2)_14") (pintype "bidirectional"))
    )
    (net (code "234") (name "unconnected-(IC2-PH7(T4)-Pad27)") (class "Default")
      (node (ref "IC2") (pin "27") (pinfunction "PH7(T4)_27") (pintype "bidirectional"))
    )
    (net (code "235") (name "unconnected-(IC2-PJ0(RXD3{slash}PCINT9)-Pad63)") (class "Default")
      (node (ref "IC2") (pin "63") (pinfunction "PJ0(RXD3/PCINT9)_63") (pintype "bidirectional"))
    )
    (net (code "236") (name "unconnected-(IC2-PJ1(TXD3{slash}PCINT10)-Pad64)") (class "Default")
      (node (ref "IC2") (pin "64") (pinfunction "PJ1(TXD3/PCINT10)_64") (pintype "bidirectional"))
    )
    (net (code "237") (name "unconnected-(IC2-PJ2(XCK3{slash}PCINT11)-Pad65)") (class "Default")
      (node (ref "IC2") (pin "65") (pinfunction "PJ2(XCK3/PCINT11)_65") (pintype "bidirectional"))
    )
    (net (code "238") (name "unconnected-(IC2-PJ3(PCINT12)-Pad66)") (class "Default")
      (node (ref "IC2") (pin "66") (pinfunction "PJ3(PCINT12)_66") (pintype "bidirectional"))
    )
    (net (code "239") (name "unconnected-(IC2-PJ4(PCINT13)-Pad67)") (class "Default")
      (node (ref "IC2") (pin "67") (pinfunction "PJ4(PCINT13)_67") (pintype "bidirectional"))
    )
    (net (code "240") (name "unconnected-(IC2-PJ5(PCINT14)-Pad68)") (class "Default")
      (node (ref "IC2") (pin "68") (pinfunction "PJ5(PCINT14)_68") (pintype "bidirectional"))
    )
    (net (code "241") (name "unconnected-(IC2-PJ6(PCINT15)-Pad69)") (class "Default")
      (node (ref "IC2") (pin "69") (pinfunction "PJ6(PCINT15)_69") (pintype "bidirectional"))
    )
    (net (code "242") (name "unconnected-(IC2-PJ7-Pad79)") (class "Default")
      (node (ref "IC2") (pin "79") (pinfunction "PJ7_79") (pintype "bidirectional"))
    )
    (net (code "243") (name "unconnected-(IC2-PK0(ADC8{slash}PCINT16)-Pad89)") (class "Default")
      (node (ref "IC2") (pin "89") (pinfunction "PK0(ADC8/PCINT16)_89") (pintype "bidirectional"))
    )
    (net (code "244") (name "unconnected-(IC2-PK1(ADC9{slash}PCINT17)-Pad88)") (class "Default")
      (node (ref "IC2") (pin "88") (pinfunction "PK1(ADC9/PCINT17)_88") (pintype "bidirectional"))
    )
    (net (code "245") (name "unconnected-(IC2-PK2(ADC10{slash}PCINT18)-Pad87)") (class "Default")
      (node (ref "IC2") (pin "87") (pinfunction "PK2(ADC10/PCINT18)_87") (pintype "bidirectional"))
    )
    (net (code "246") (name "unconnected-(IC2-PK3(ADC11{slash}PCINT19)-Pad86)") (class "Default")
      (node (ref "IC2") (pin "86") (pinfunction "PK3(ADC11/PCINT19)_86") (pintype "bidirectional"))
    )
    (net (code "247") (name "unconnected-(IC2-PK4(ADC12{slash}PCINT20)-Pad85)") (class "Default")
      (node (ref "IC2") (pin "85") (pinfunction "PK4(ADC12/PCINT20)_85") (pintype "bidirectional"))
    )
    (net (code "248") (name "unconnected-(IC2-PK5(ADC13{slash}PCINT21)-Pad84)") (class "Default")
      (node (ref "IC2") (pin "84") (pinfunction "PK5(ADC13/PCINT21)_84") (pintype "bidirectional"))
    )
    (net (code "249") (name "unconnected-(IC2-PK6(ADC14{slash}PCINT22)-Pad83)") (class "Default")
      (node (ref "IC2") (pin "83") (pinfunction "PK6(ADC14/PCINT22)_83") (pintype "bidirectional"))
    )
    (net (code "250") (name "unconnected-(IC2-PK7(ADC15{slash}PCINT23)-Pad82)") (class "Default")
      (node (ref "IC2") (pin "82") (pinfunction "PK7(ADC15/PCINT23)_82") (pintype "bidirectional"))
    )
    (net (code "251") (name "unconnected-(IC2-PL0(ICP4)-Pad35)") (class "Default")
      (node (ref "IC2") (pin "35") (pinfunction "PL0(ICP4)_35") (pintype "bidirectional"))
    )
    (net (code "252") (name "unconnected-(IC2-PL1(ICP5)-Pad36)") (class "Default")
      (node (ref "IC2") (pin "36") (pinfunction "PL1(ICP5)_36") (pintype "bidirectional"))
    )
    (net (code "253") (name "unconnected-(IC2-PL2(T5)-Pad37)") (class "Default")
      (node (ref "IC2") (pin "37") (pinfunction "PL2(T5)_37") (pintype "bidirectional"))
    )
    (net (code "254") (name "unconnected-(IC2-PL3(OC5A)-Pad38)") (class "Default")
      (node (ref "IC2") (pin "38") (pinfunction "PL3(OC5A)_38") (pintype "bidirectional"))
    )
    (net (code "255") (name "unconnected-(IC2-PL4(OC5B)-Pad39)") (class "Default")
      (node (ref "IC2") (pin "39") (pinfunction "PL4(OC5B)_39") (pintype "bidirectional"))
    )
    (net (code "256") (name "unconnected-(IC2-PL5(OC5C)-Pad40)") (class "Default")
      (node (ref "IC2") (pin "40") (pinfunction "PL5(OC5C)_40") (pintype "bidirectional"))
    )
    (net (code "257") (name "unconnected-(IC2-PL6-Pad41)") (class "Default")
      (node (ref "IC2") (pin "41") (pinfunction "PL6_41") (pintype "bidirectional"))
    )
    (net (code "258") (name "unconnected-(IC2-PL7-Pad42)") (class "Default")
      (node (ref "IC2") (pin "42") (pinfunction "PL7_42") (pintype "bidirectional"))
    )
    (net (code "259") (name "unconnected-(IC3-(A8)PC0-Pad53)") (class "Default")
      (node (ref "IC3") (pin "53") (pinfunction "(A8)PC0_53") (pintype "bidirectional"))
    )
    (net (code "260") (name "unconnected-(IC3-(A9)PC1-Pad54)") (class "Default")
      (node (ref "IC3") (pin "54") (pinfunction "(A9)PC1_54") (pintype "bidirectional"))
    )
    (net (code "261") (name "unconnected-(IC3-(A10)PC2-Pad55)") (class "Default")
      (node (ref "IC3") (pin "55") (pinfunction "(A10)PC2_55") (pintype "bidirectional"))
    )
    (net (code "262") (name "unconnected-(IC3-(A11)PC3-Pad56)") (class "Default")
      (node (ref "IC3") (pin "56") (pinfunction "(A11)PC3_56") (pintype "bidirectional"))
    )
    (net (code "263") (name "unconnected-(IC3-(A12)PC4-Pad57)") (class "Default")
      (node (ref "IC3") (pin "57") (pinfunction "(A12)PC4_57") (pintype "bidirectional"))
    )
    (net (code "264") (name "unconnected-(IC3-(A13)PC5-Pad58)") (class "Default")
      (node (ref "IC3") (pin "58") (pinfunction "(A13)PC5_58") (pintype "bidirectional"))
    )
    (net (code "265") (name "unconnected-(IC3-(A14)PC6-Pad59)") (class "Default")
      (node (ref "IC3") (pin "59") (pinfunction "(A14)PC6_59") (pintype "bidirectional"))
    )
    (net (code "266") (name "unconnected-(IC3-(A15)PC7-Pad60)") (class "Default")
      (node (ref "IC3") (pin "60") (pinfunction "(A15)PC7_60") (pintype "bidirectional"))
    )
    (net (code "267") (name "unconnected-(IC3-(AD0)PA0-Pad78)") (class "Default")
      (node (ref "IC3") (pin "78") (pinfunction "(AD0)PA0_78") (pintype "bidirectional"))
    )
    (net (code "268") (name "unconnected-(IC3-(AD1)PA1-Pad77)") (class "Default")
      (node (ref "IC3") (pin "77") (pinfunction "(AD1)PA1_77") (pintype "bidirectional"))
    )
    (net (code "269") (name "unconnected-(IC3-(AD2)PA2-Pad76)") (class "Default")
      (node (ref "IC3") (pin "76") (pinfunction "(AD2)PA2_76") (pintype "bidirectional"))
    )
    (net (code "270") (name "unconnected-(IC3-(AD3)PA3-Pad75)") (class "Default")
      (node (ref "IC3") (pin "75") (pinfunction "(AD3)PA3_75") (pintype "bidirectional"))
    )
    (net (code "271") (name "unconnected-(IC3-(AD4)PA4-Pad74)") (class "Default")
      (node (ref "IC3") (pin "74") (pinfunction "(AD4)PA4_74") (pintype "bidirectional"))
    )
    (net (code "272") (name "unconnected-(IC3-(AD5)PA5-Pad73)") (class "Default")
      (node (ref "IC3") (pin "73") (pinfunction "(AD5)PA5_73") (pintype "bidirectional"))
    )
    (net (code "273") (name "unconnected-(IC3-(AD6)PA6-Pad72)") (class "Default")
      (node (ref "IC3") (pin "72") (pinfunction "(AD6)PA6_72") (pintype "bidirectional"))
    )
    (net (code "274") (name "unconnected-(IC3-(AD7)PA7-Pad71)") (class "Default")
      (node (ref "IC3") (pin "71") (pinfunction "(AD7)PA7_71") (pintype "bidirectional"))
    )
    (net (code "275") (name "unconnected-(IC3-(ADC1)PF1-Pad96)") (class "Default")
      (node (ref "IC3") (pin "96") (pinfunction "(ADC1)PF1_96") (pintype "bidirectional"))
    )
    (net (code "276") (name "unconnected-(IC3-(ADC2)PF2-Pad95)") (class "Default")
      (node (ref "IC3") (pin "95") (pinfunction "(ADC2)PF2_95") (pintype "bidirectional"))
    )
    (net (code "277") (name "unconnected-(IC3-(ADC3)PF3-Pad94)") (class "Default")
      (node (ref "IC3") (pin "94") (pinfunction "(ADC3)PF3_94") (pintype "bidirectional"))
    )
    (net (code "278") (name "unconnected-(IC3-(ADC4{slash}TCK)PF4-Pad93)") (class "Default")
      (node (ref "IC3") (pin "93") (pinfunction "(ADC4/TCK)PF4_93") (pintype "bidirectional"))
    )
    (net (code "279") (name "unconnected-(IC3-(ADC5{slash}TMS)PF5-Pad92)") (class "Default")
      (node (ref "IC3") (pin "92") (pinfunction "(ADC5/TMS)PF5_92") (pintype "bidirectional"))
    )
    (net (code "280") (name "unconnected-(IC3-(ADC6{slash}TDO)PF6-Pad91)") (class "Default")
      (node (ref "IC3") (pin "91") (pinfunction "(ADC6/TDO)PF6_91") (pintype "bidirectional"))
    )
    (net (code "281") (name "unconnected-(IC3-(ADC7{slash}TDI)PF7-Pad90)") (class "Default")
      (node (ref "IC3") (pin "90") (pinfunction "(ADC7/TDI)PF7_90") (pintype "bidirectional"))
    )
    (net (code "282") (name "unconnected-(IC3-(ALE)PG2-Pad70)") (class "Default")
      (node (ref "IC3") (pin "70") (pinfunction "(ALE)PG2_70") (pintype "bidirectional"))
    )
    (net (code "283") (name "unconnected-(IC3-(CLKO{slash}ICP3{slash}INT7)PE7-Pad9)") (class "Default")
      (node (ref "IC3") (pin "9") (pinfunction "(CLKO/ICP3/INT7)PE7_9") (pintype "bidirectional"))
    )
    (net (code "284") (name "unconnected-(IC3-(ICP1)PD4-Pad47)") (class "Default")
      (node (ref "IC3") (pin "47") (pinfunction "(ICP1)PD4_47") (pintype "bidirectional"))
    )
    (net (code "285") (name "unconnected-(IC3-(OC0A{slash}OC1C{slash}PCINT7)PB7-Pad26)") (class "Default")
      (node (ref "IC3") (pin "26") (pinfunction "(OC0A/OC1C/PCINT7)PB7_26") (pintype "bidirectional"))
    )
    (net (code "286") (name "unconnected-(IC3-(OC3B{slash}INT4)PE4-Pad6)") (class "Default")
      (node (ref "IC3") (pin "6") (pinfunction "(OC3B/INT4)PE4_6") (pintype "bidirectional"))
    )
    (net (code "287") (name "unconnected-(IC3-(RD)PG1-Pad52)") (class "Default")
      (node (ref "IC3") (pin "52") (pinfunction "(RD)PG1_52") (pintype "bidirectional"))
    )
    (net (code "288") (name "unconnected-(IC3-(T0)PD7-Pad50)") (class "Default")
      (node (ref "IC3") (pin "50") (pinfunction "(T0)PD7_50") (pintype "bidirectional"))
    )
    (net (code "289") (name "unconnected-(IC3-(T1)PD6-Pad49)") (class "Default")
      (node (ref "IC3") (pin "49") (pinfunction "(T1)PD6_49") (pintype "bidirectional"))
    )
    (net (code "290") (name "unconnected-(IC3-(T3{slash}INT6)PE6-Pad8)") (class "Default")
      (node (ref "IC3") (pin "8") (pinfunction "(T3/INT6)PE6_8") (pintype "bidirectional"))
    )
    (net (code "291") (name "unconnected-(IC3-(TOSC1)PG4-Pad29)") (class "Default")
      (node (ref "IC3") (pin "29") (pinfunction "(TOSC1)PG4_29") (pintype "bidirectional"))
    )
    (net (code "292") (name "unconnected-(IC3-(TOSC2)PG3-Pad28)") (class "Default")
      (node (ref "IC3") (pin "28") (pinfunction "(TOSC2)PG3_28") (pintype "bidirectional"))
    )
    (net (code "293") (name "unconnected-(IC3-(WR)PG0-Pad51)") (class "Default")
      (node (ref "IC3") (pin "51") (pinfunction "(WR)PG0_51") (pintype "bidirectional"))
    )
    (net (code "294") (name "unconnected-(IC3-(XCK0{slash}AIN0)PE2-Pad4)") (class "Default")
      (node (ref "IC3") (pin "4") (pinfunction "(XCK0/AIN0)PE2_4") (pintype "bidirectional"))
    )
    (net (code "295") (name "unconnected-(IC3-(XCK1)PD5-Pad48)") (class "Default")
      (node (ref "IC3") (pin "48") (pinfunction "(XCK1)PD5_48") (pintype "bidirectional"))
    )
    (net (code "296") (name "unconnected-(IC3-PH0(RXD2)-Pad12)") (class "Default")
      (node (ref "IC3") (pin "12") (pinfunction "PH0(RXD2)_12") (pintype "bidirectional"))
    )
    (net (code "297") (name "unconnected-(IC3-PH1(TXD2)-Pad13)") (class "Default")
      (node (ref "IC3") (pin "13") (pinfunction "PH1(TXD2)_13") (pintype "bidirectional"))
    )
    (net (code "298") (name "unconnected-(IC3-PH2(XCK2)-Pad14)") (class "Default")
      (node (ref "IC3") (pin "14") (pinfunction "PH2(XCK2)_14") (pintype "bidirectional"))
    )
    (net (code "299") (name "unconnected-(IC3-PH7(T4)-Pad27)") (class "Default")
      (node (ref "IC3") (pin "27") (pinfunction "PH7(T4)_27") (pintype "bidirectional"))
    )
    (net (code "300") (name "unconnected-(IC3-PJ0(RXD3{slash}PCINT9)-Pad63)") (class "Default")
      (node (ref "IC3") (pin "63") (pinfunction "PJ0(RXD3/PCINT9)_63") (pintype "bidirectional"))
    )
    (net (code "301") (name "unconnected-(IC3-PJ1(TXD3{slash}PCINT10)-Pad64)") (class "Default")
      (node (ref "IC3") (pin "64") (pinfunction "PJ1(TXD3/PCINT10)_64") (pintype "bidirectional"))
    )
    (net (code "302") (name "unconnected-(IC3-PJ2(XCK3{slash}PCINT11)-Pad65)") (class "Default")
      (node (ref "IC3") (pin "65") (pinfunction "PJ2(XCK3/PCINT11)_65") (pintype "bidirectional"))
    )
    (net (code "303") (name "unconnected-(IC3-PJ3(PCINT12)-Pad66)") (class "Default")
      (node (ref "IC3") (pin "66") (pinfunction "PJ3(PCINT12)_66") (pintype "bidirectional"))
    )
    (net (code "304") (name "unconnected-(IC3-PJ4(PCINT13)-Pad67)") (class "Default")
      (node (ref "IC3") (pin "67") (pinfunction "PJ4(PCINT13)_67") (pintype "bidirectional"))
    )
    (net (code "305") (name "unconnected-(IC3-PJ5(PCINT14)-Pad68)") (class "Default")
      (node (ref "IC3") (pin "68") (pinfunction "PJ5(PCINT14)_68") (pintype "bidirectional"))
    )
    (net (code "306") (name "unconnected-(IC3-PJ6(PCINT15)-Pad69)") (class "Default")
      (node (ref "IC3") (pin "69") (pinfunction "PJ6(PCINT15)_69") (pintype "bidirectional"))
    )
    (net (code "307") (name "unconnected-(IC3-PJ7-Pad79)") (class "Default")
      (node (ref "IC3") (pin "79") (pinfunction "PJ7_79") (pintype "bidirectional"))
    )
    (net (code "308") (name "unconnected-(IC3-PK0(ADC8{slash}PCINT16)-Pad89)") (class "Default")
      (node (ref "IC3") (pin "89") (pinfunction "PK0(ADC8/PCINT16)_89") (pintype "bidirectional"))
    )
    (net (code "309") (name "unconnected-(IC3-PK1(ADC9{slash}PCINT17)-Pad88)") (class "Default")
      (node (ref "IC3") (pin "88") (pinfunction "PK1(ADC9/PCINT17)_88") (pintype "bidirectional"))
    )
    (net (code "310") (name "unconnected-(IC3-PK2(ADC10{slash}PCINT18)-Pad87)") (class "Default")
      (node (ref "IC3") (pin "87") (pinfunction "PK2(ADC10/PCINT18)_87") (pintype "bidirectional"))
    )
    (net (code "311") (name "unconnected-(IC3-PK3(ADC11{slash}PCINT19)-Pad86)") (class "Default")
      (node (ref "IC3") (pin "86") (pinfunction "PK3(ADC11/PCINT19)_86") (pintype "bidirectional"))
    )
    (net (code "312") (name "unconnected-(IC3-PK4(ADC12{slash}PCINT20)-Pad85)") (class "Default")
      (node (ref "IC3") (pin "85") (pinfunction "PK4(ADC12/PCINT20)_85") (pintype "bidirectional"))
    )
    (net (code "313") (name "unconnected-(IC3-PK5(ADC13{slash}PCINT21)-Pad84)") (class "Default")
      (node (ref "IC3") (pin "84") (pinfunction "PK5(ADC13/PCINT21)_84") (pintype "bidirectional"))
    )
    (net (code "314") (name "unconnected-(IC3-PK6(ADC14{slash}PCINT22)-Pad83)") (class "Default")
      (node (ref "IC3") (pin "83") (pinfunction "PK6(ADC14/PCINT22)_83") (pintype "bidirectional"))
    )
    (net (code "315") (name "unconnected-(IC3-PK7(ADC15{slash}PCINT23)-Pad82)") (class "Default")
      (node (ref "IC3") (pin "82") (pinfunction "PK7(ADC15/PCINT23)_82") (pintype "bidirectional"))
    )
    (net (code "316") (name "unconnected-(IC3-PL0(ICP4)-Pad35)") (class "Default")
      (node (ref "IC3") (pin "35") (pinfunction "PL0(ICP4)_35") (pintype "bidirectional"))
    )
    (net (code "317") (name "unconnected-(IC3-PL1(ICP5)-Pad36)") (class "Default")
      (node (ref "IC3") (pin "36") (pinfunction "PL1(ICP5)_36") (pintype "bidirectional"))
    )
    (net (code "318") (name "unconnected-(IC3-PL2(T5)-Pad37)") (class "Default")
      (node (ref "IC3") (pin "37") (pinfunction "PL2(T5)_37") (pintype "bidirectional"))
    )
    (net (code "319") (name "unconnected-(IC3-PL3(OC5A)-Pad38)") (class "Default")
      (node (ref "IC3") (pin "38") (pinfunction "PL3(OC5A)_38") (pintype "bidirectional"))
    )
    (net (code "320") (name "unconnected-(IC3-PL4(OC5B)-Pad39)") (class "Default")
      (node (ref "IC3") (pin "39") (pinfunction "PL4(OC5B)_39") (pintype "bidirectional"))
    )
    (net (code "321") (name "unconnected-(IC3-PL5(OC5C)-Pad40)") (class "Default")
      (node (ref "IC3") (pin "40") (pinfunction "PL5(OC5C)_40") (pintype "bidirectional"))
    )
    (net (code "322") (name "unconnected-(IC3-PL6-Pad41)") (class "Default")
      (node (ref "IC3") (pin "41") (pinfunction "PL6_41") (pintype "bidirectional"))
    )
    (net (code "323") (name "unconnected-(IC3-PL7-Pad42)") (class "Default")
      (node (ref "IC3") (pin "42") (pinfunction "PL7_42") (pintype "bidirectional"))
    )
    (net (code "324") (name "unconnected-(IC4-I+_1-Pad2)") (class "Default")
      (node (ref "IC4") (pin "2") (pinfunction "I+_1_2") (pintype "bidirectional"))
    )
    (net (code "325") (name "unconnected-(IC4-I-_1-Pad4)") (class "Default")
      (node (ref "IC4") (pin "4") (pinfunction "I-_1_4") (pintype "bidirectional"))
    )
    (net (code "326") (name "unconnected-(IC5-I+_1-Pad2)") (class "Default")
      (node (ref "IC5") (pin "2") (pinfunction "I+_1_2") (pintype "bidirectional"))
    )
    (net (code "327") (name "unconnected-(IC5-I-_1-Pad4)") (class "Default")
      (node (ref "IC5") (pin "4") (pinfunction "I-_1_4") (pintype "bidirectional"))
    )
    (net (code "328") (name "unconnected-(IC6-I+_1-Pad2)") (class "Default")
      (node (ref "IC6") (pin "2") (pinfunction "I+_1_2") (pintype "bidirectional"))
    )
    (net (code "329") (name "unconnected-(IC6-I-_1-Pad4)") (class "Default")
      (node (ref "IC6") (pin "4") (pinfunction "I-_1_4") (pintype "bidirectional"))
    )
    (net (code "330") (name "unconnected-(JP1-Pad13)") (class "Default")
      (node (ref "JP1") (pin "13") (pinfunction "13_13") (pintype "passive"))
    )
    (net (code "331") (name "unconnected-(JP1-Pad14)") (class "Default")
      (node (ref "JP1") (pin "14") (pinfunction "14_14") (pintype "passive"))
    )
    (net (code "332") (name "unconnected-(JP1-Pad15)") (class "Default")
      (node (ref "JP1") (pin "15") (pinfunction "15_15") (pintype "passive"))
    )
    (net (code "333") (name "unconnected-(JP1-Pad16)") (class "Default")
      (node (ref "JP1") (pin "16") (pinfunction "16_16") (pintype "passive"))
    )
    (net (code "334") (name "unconnected-(JP1-Pad18)") (class "Default")
      (node (ref "JP1") (pin "18") (pinfunction "18_18") (pintype "passive"))
    )
    (net (code "335") (name "unconnected-(JP1-Pad20)") (class "Default")
      (node (ref "JP1") (pin "20") (pinfunction "20_20") (pintype "passive"))
    )
    (net (code "336") (name "unconnected-(JP1-Pad21)") (class "Default")
      (node (ref "JP1") (pin "21") (pinfunction "21_21") (pintype "passive"))
    )
    (net (code "337") (name "unconnected-(JP1-Pad22)") (class "Default")
      (node (ref "JP1") (pin "22") (pinfunction "22_22") (pintype "passive"))
    )
    (net (code "338") (name "unconnected-(JP1-Pad24)") (class "Default")
      (node (ref "JP1") (pin "24") (pinfunction "24_24") (pintype "passive"))
    )
    (net (code "339") (name "unconnected-(JP1-Pad26)") (class "Default")
      (node (ref "JP1") (pin "26") (pinfunction "26_26") (pintype "passive"))
    )
  )
)
